# IVEEDRIS-SCIR.net
KiCad netlist of a schematic drawn in EAGLE
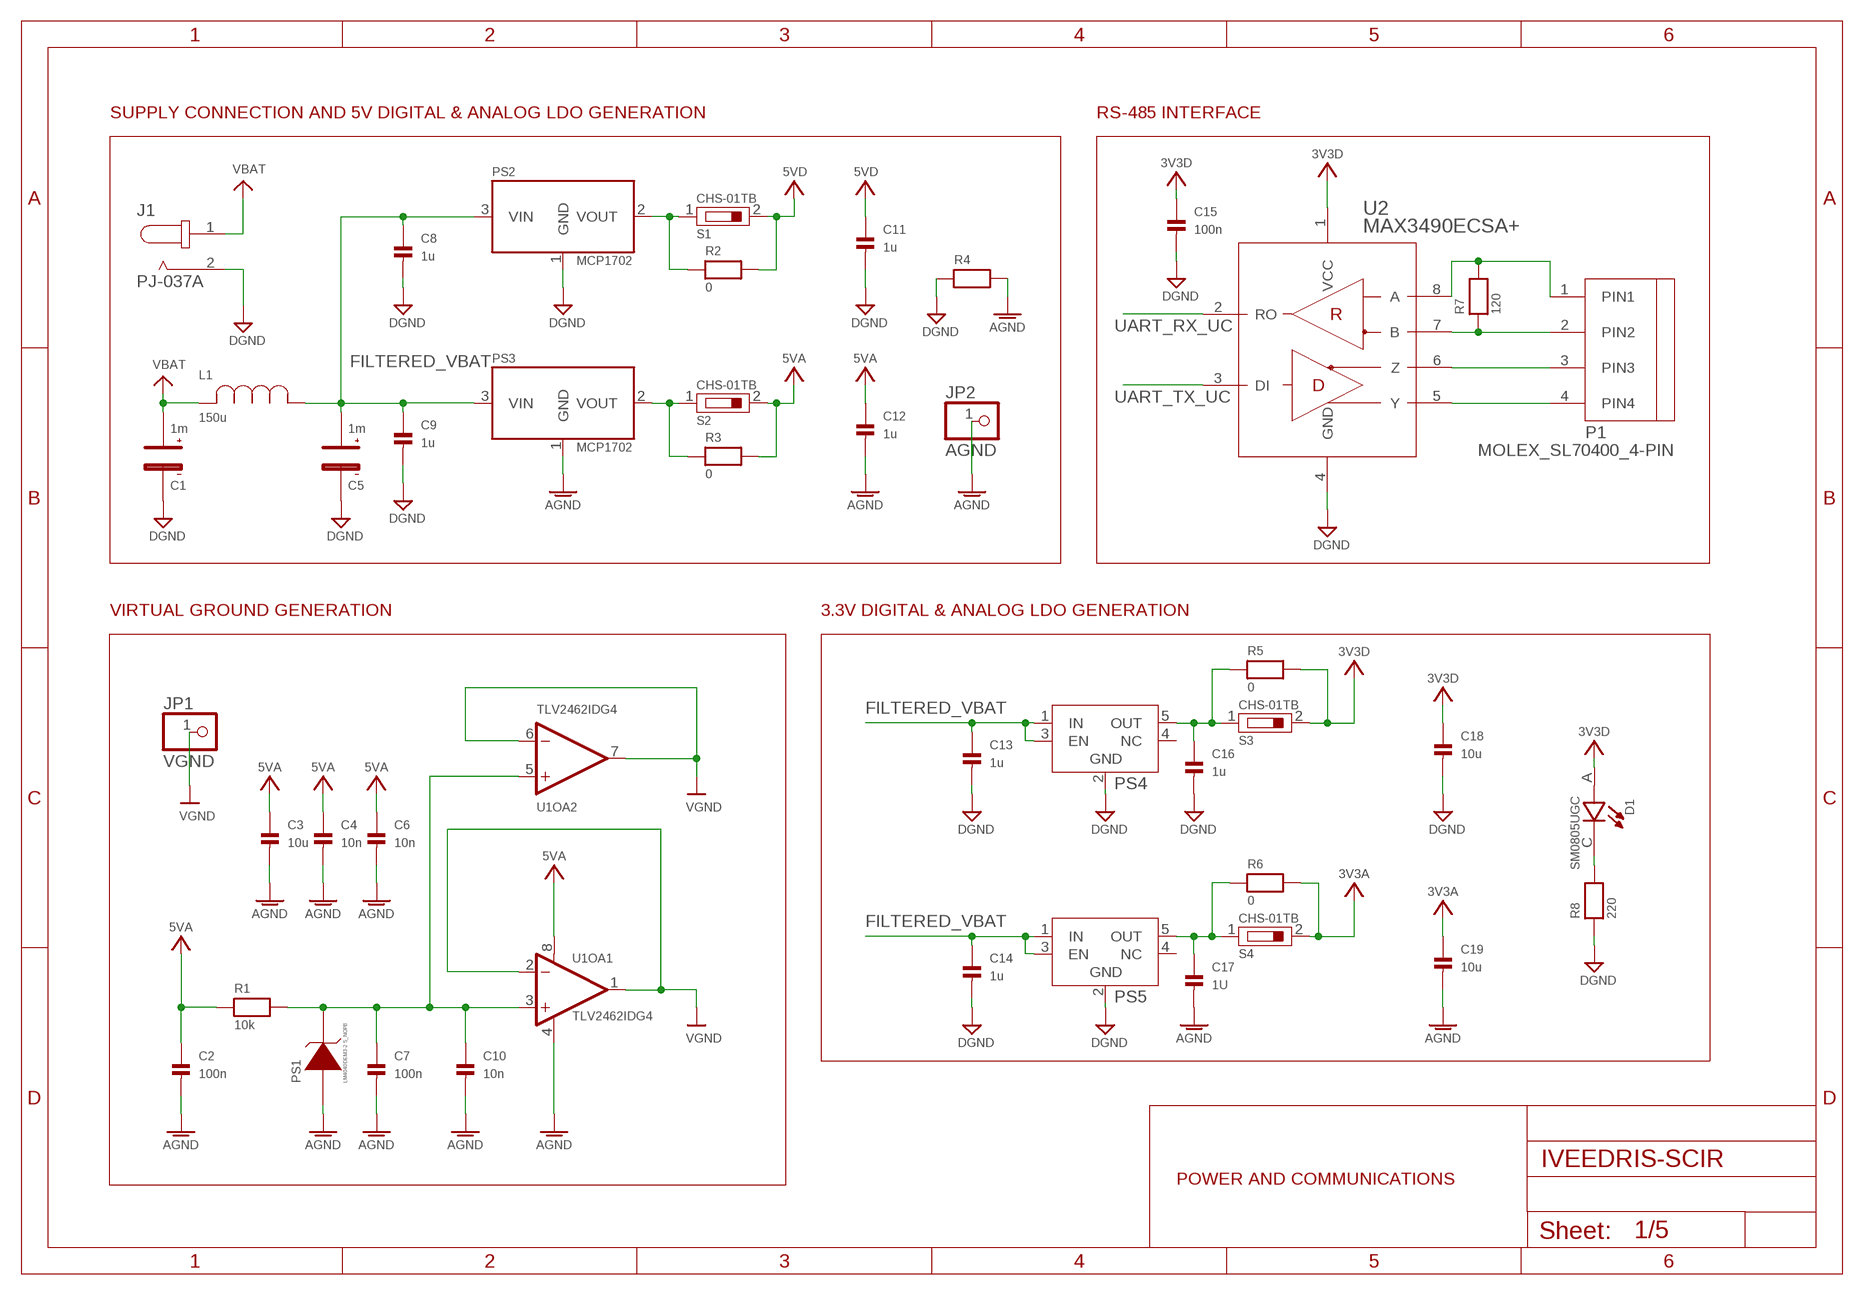
[diagram p0: schematic, sheet 1]
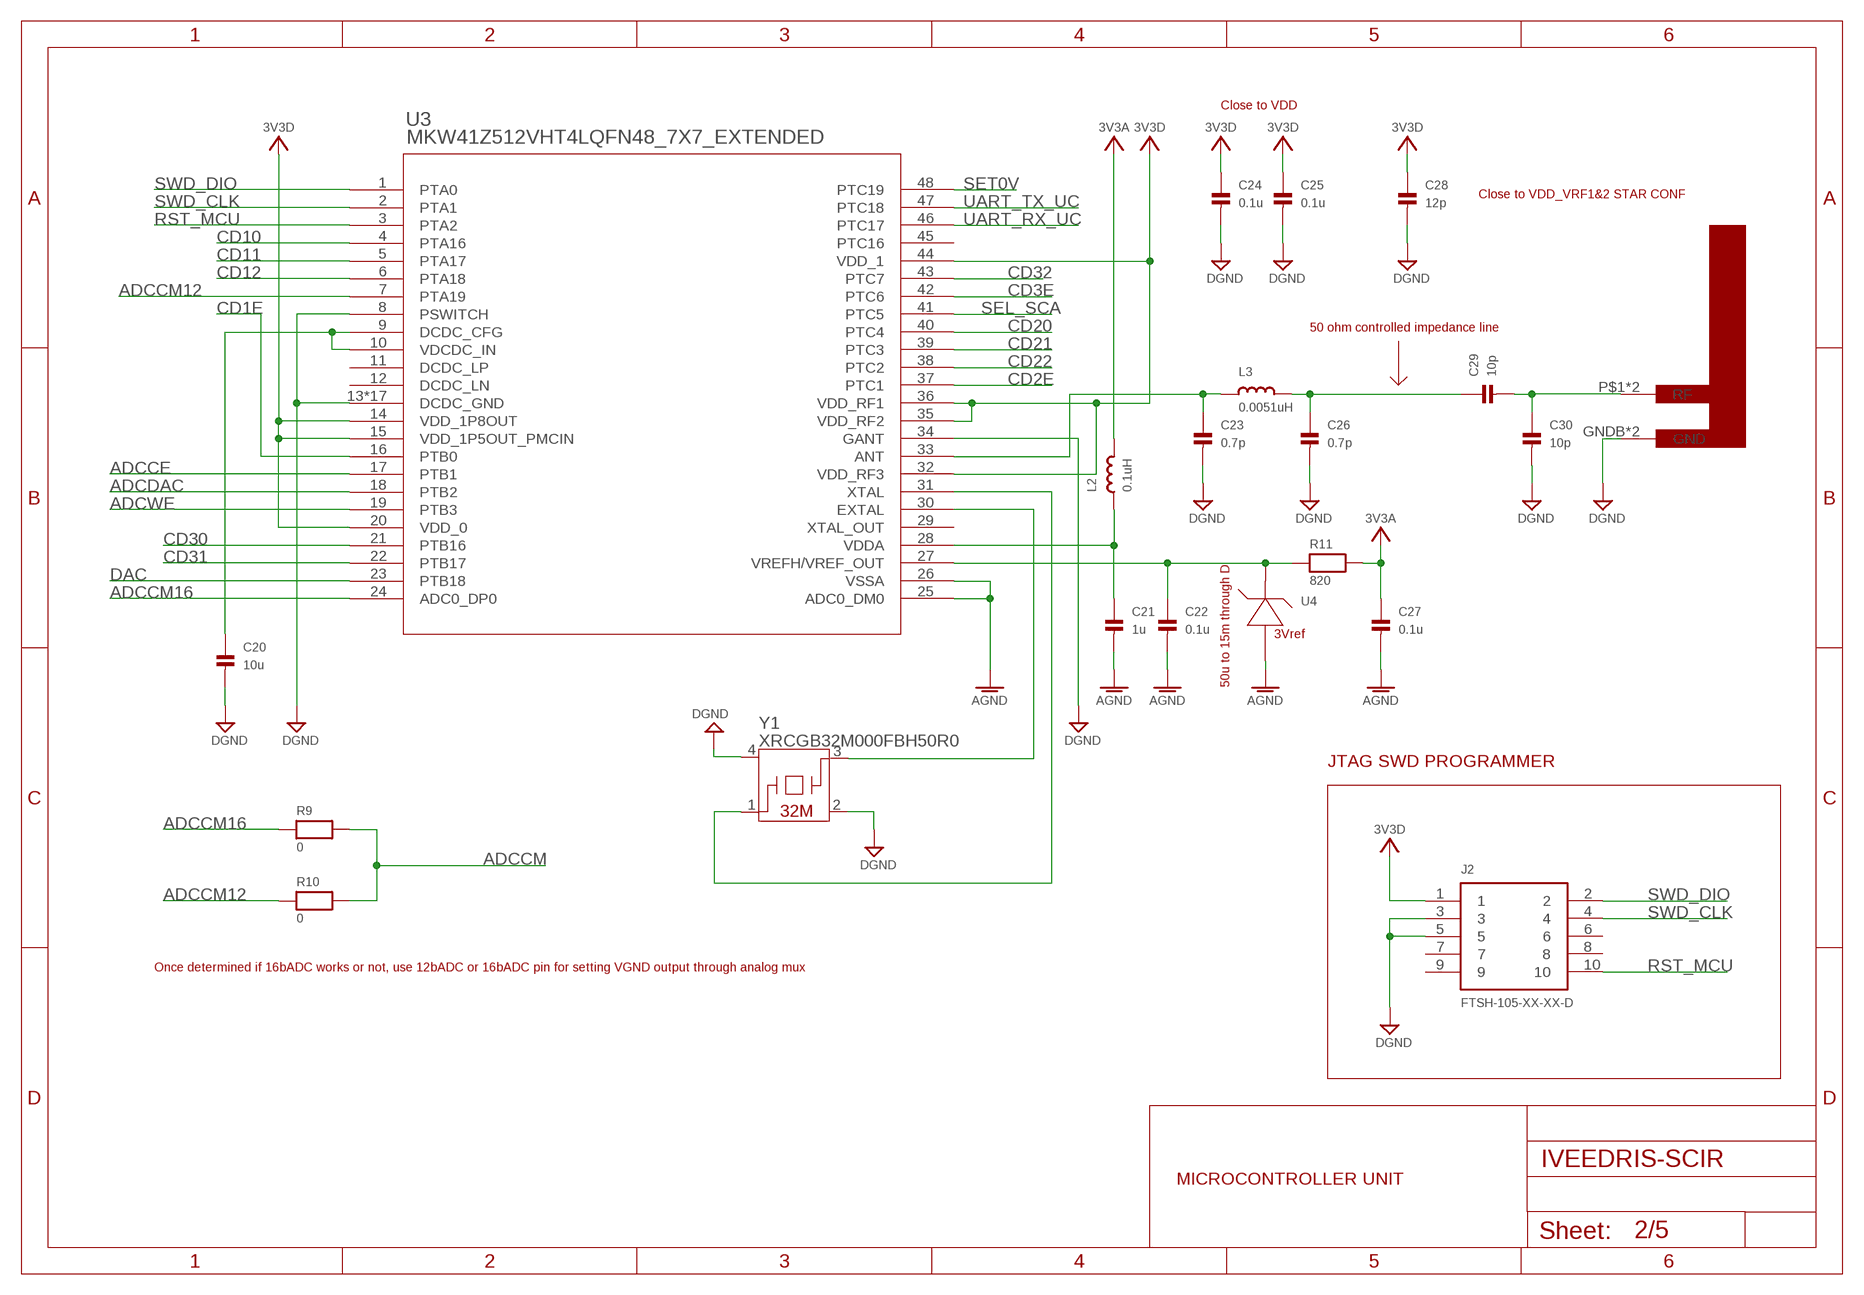
[diagram p1: schematic, sheet 2]
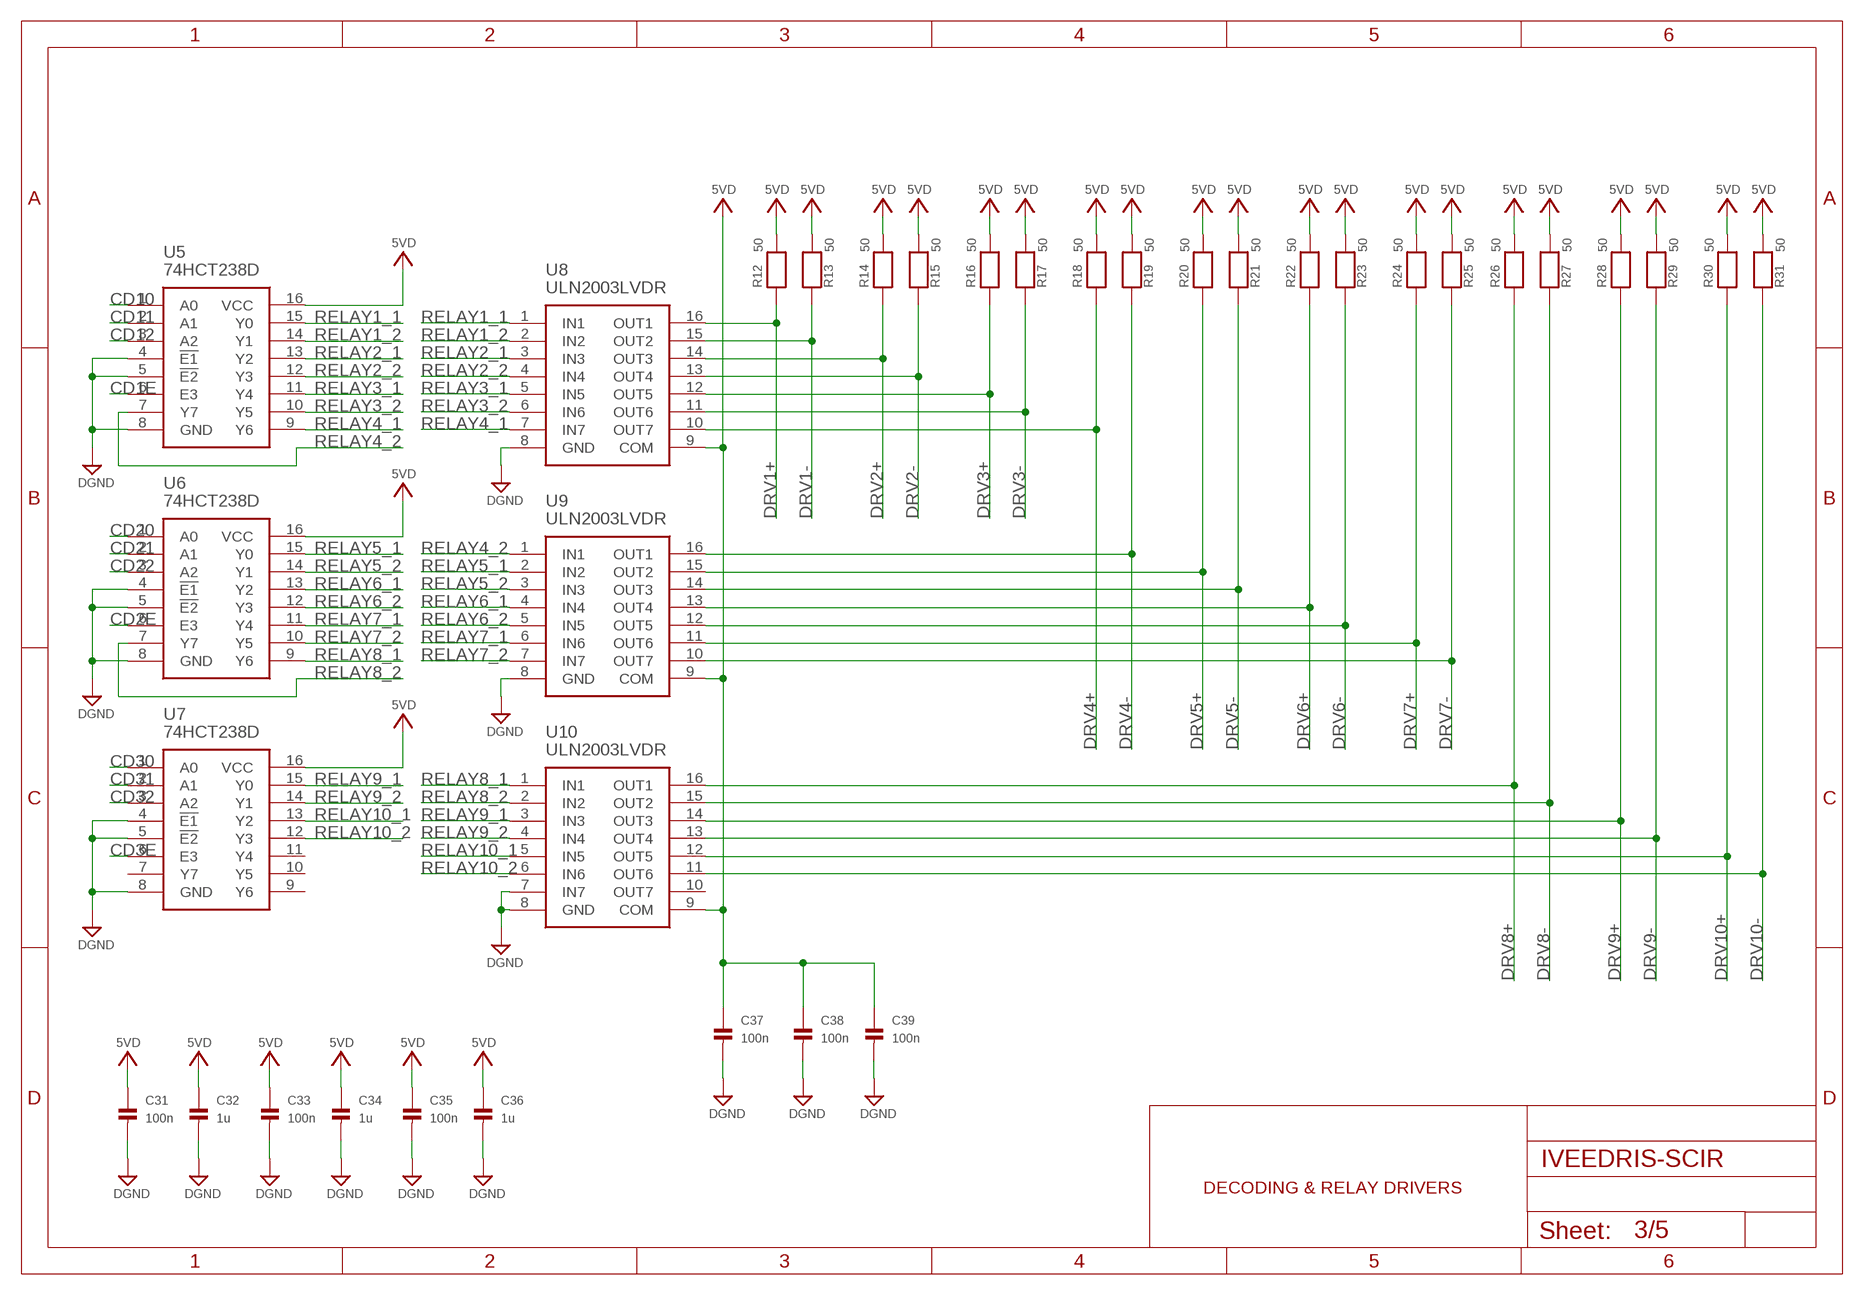
[diagram p2: schematic, sheet 3]
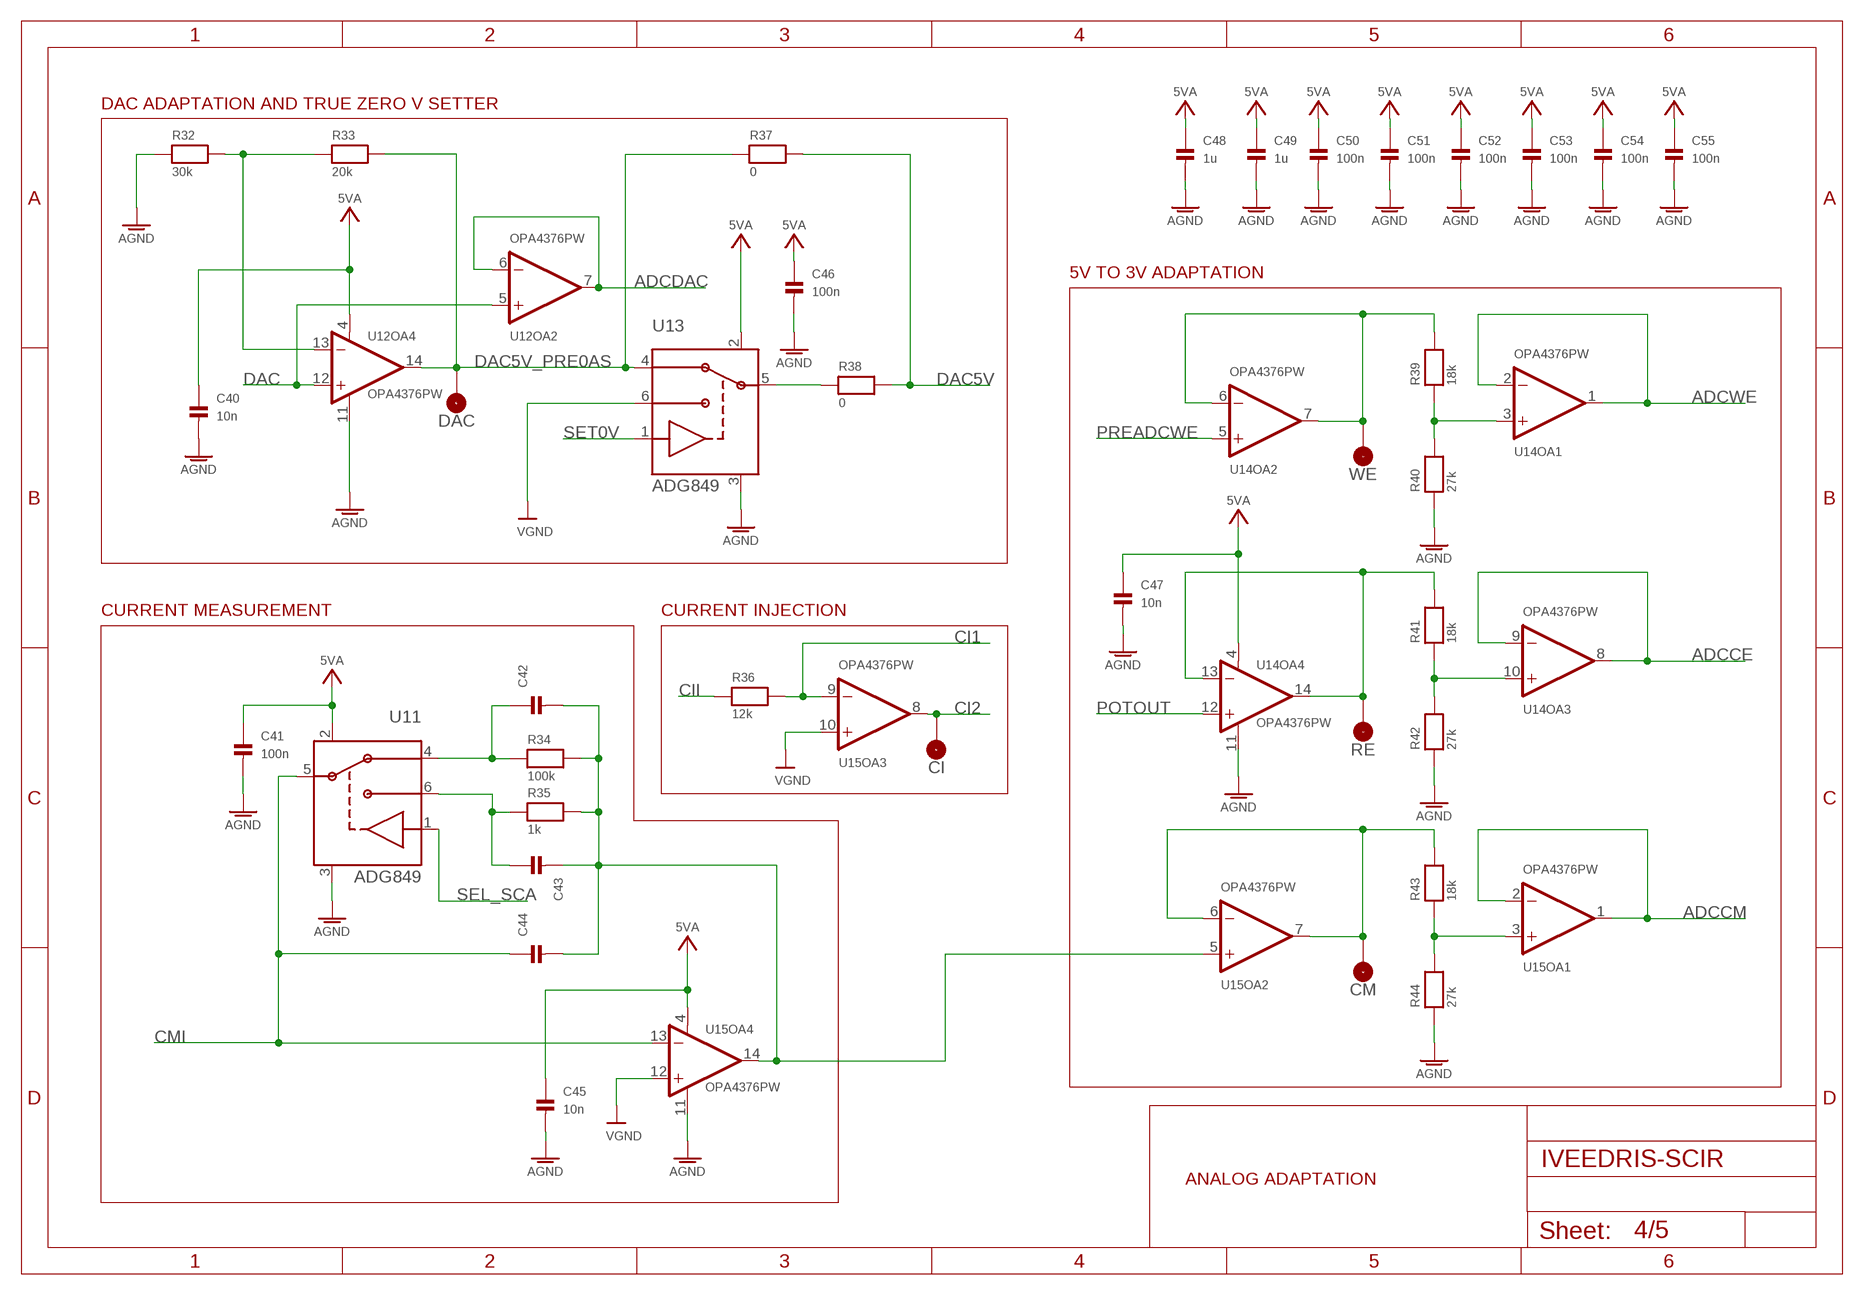
[diagram p3: schematic, sheet 4]
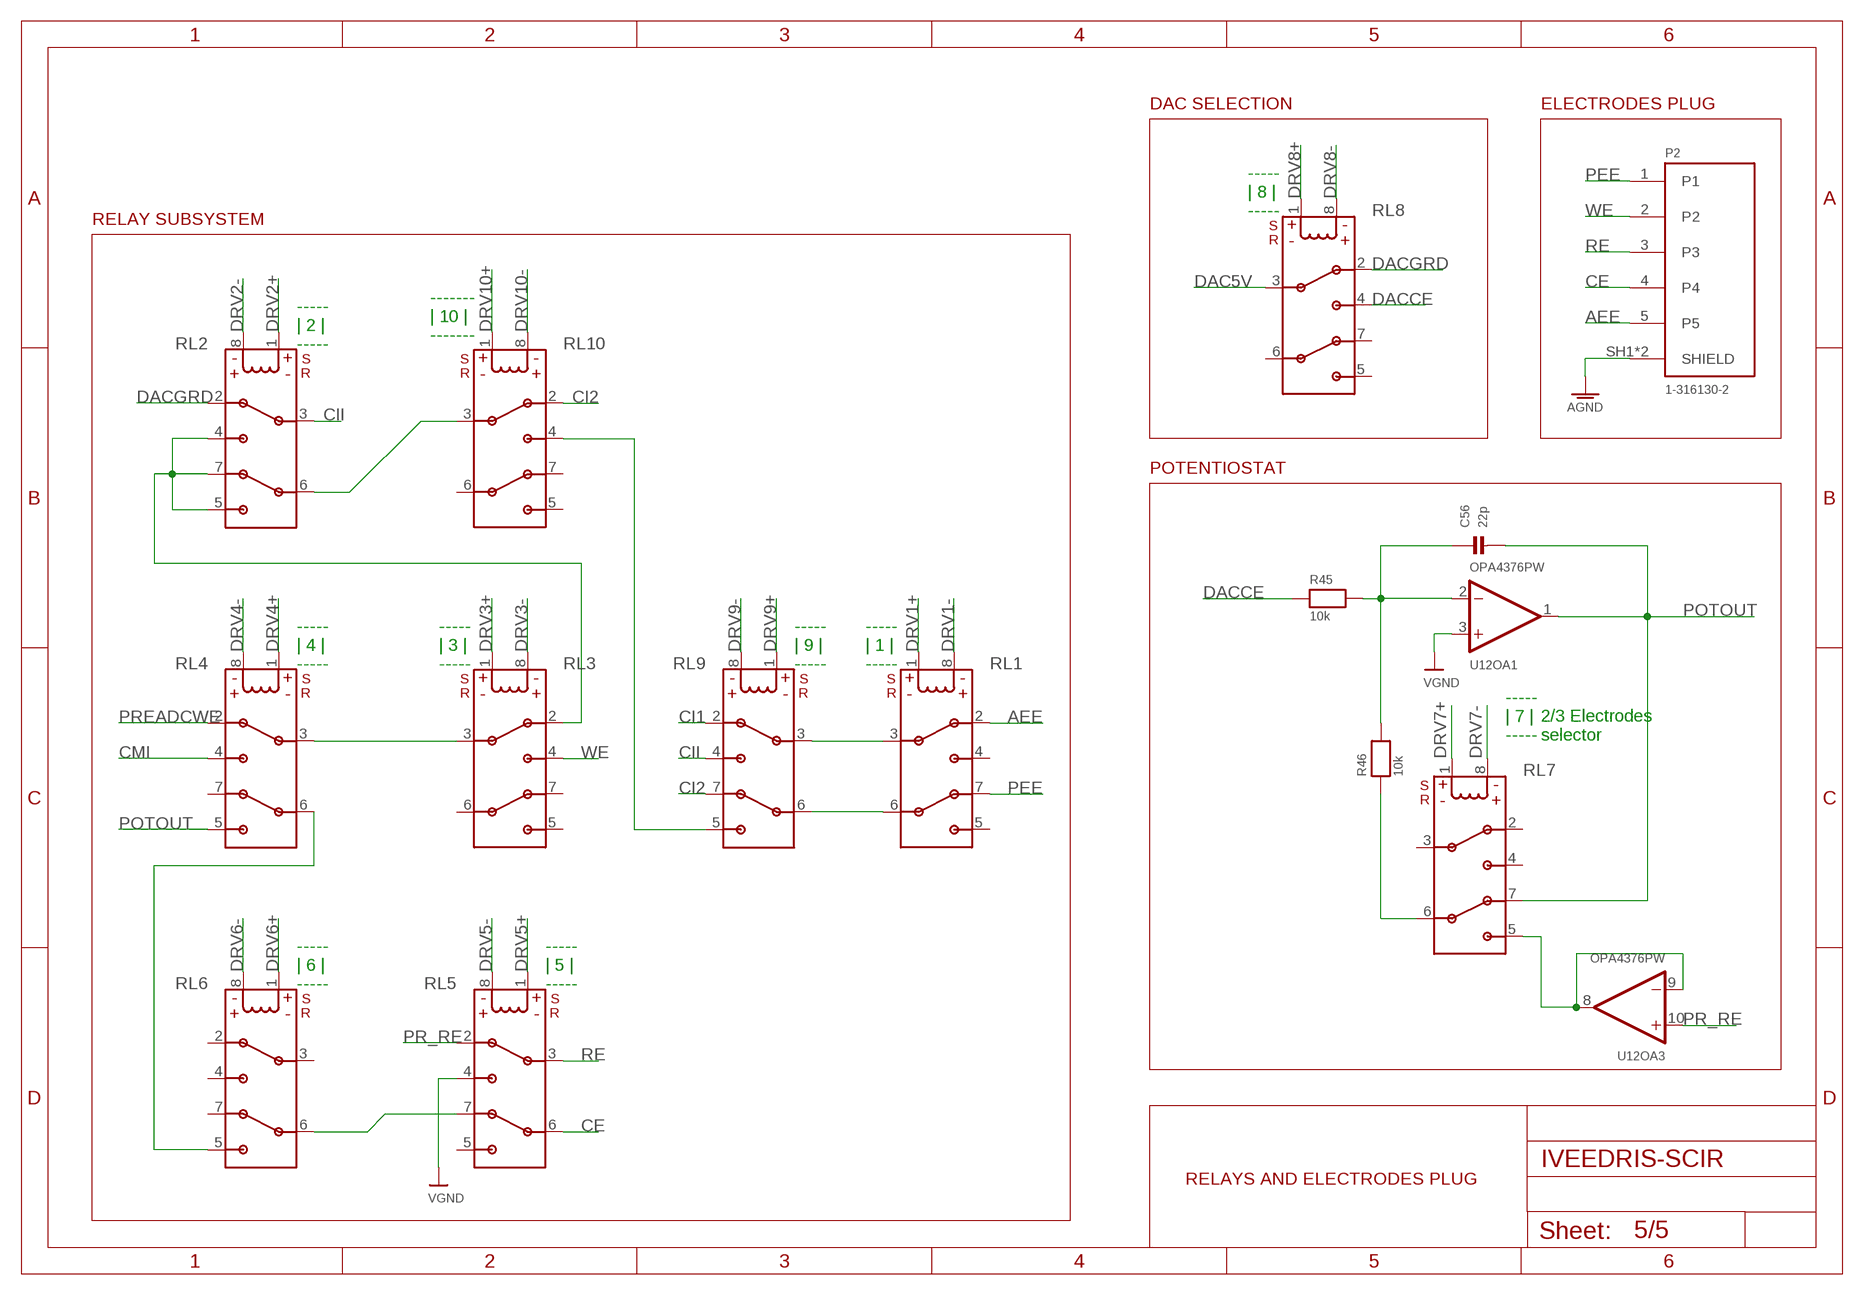
[diagram p4: schematic, sheet 5]

(export (version "E")
  (design (tool "Eeschema 10.0.6"))
  (components
    (comp (ref "C56")
      (value "22p")
      (footprint "eagle-import:0805")
      (libsource (lib "eagle-import") (part "CAP_CERAMIC0805"))
    )
    (comp (ref "P2")
      (value "1-316130-2")
      (footprint "eagle-import:TE_1-316130-2")
      (libsource (lib "eagle-import") (part "1-316130-2"))
    )
    (comp (ref "R45")
      (value "10k")
      (footprint "eagle-import:0805")
      (libsource (lib "eagle-import") (part "RESISTOR0805"))
    )
    (comp (ref "R46")
      (value "10k")
      (footprint "eagle-import:0805")
      (libsource (lib "eagle-import") (part "RESISTOR0805"))
    )
    (comp (ref "RL1")
      (value "G6KU-2F-Y")
      (footprint "eagle-import:G6KU-2F-Y")
      (fields (field (name "MANUFACTURER_PART_NUMBER") "G6KU-2F-Y DC5"))
      (libsource (lib "eagle-import") (part "G6KU-2F-Y"))
    )
    (comp (ref "RL2")
      (value "G6KU-2F-Y")
      (footprint "eagle-import:G6KU-2F-Y")
      (fields (field (name "MANUFACTURER_PART_NUMBER") "G6KU-2F-Y DC5"))
      (libsource (lib "eagle-import") (part "G6KU-2F-Y"))
    )
    (comp (ref "RL3")
      (value "G6KU-2F-Y")
      (footprint "eagle-import:G6KU-2F-Y")
      (fields (field (name "MANUFACTURER_PART_NUMBER") "G6KU-2F-Y DC5"))
      (libsource (lib "eagle-import") (part "G6KU-2F-Y"))
    )
    (comp (ref "RL4")
      (value "G6KU-2F-Y")
      (footprint "eagle-import:G6KU-2F-Y")
      (fields (field (name "MANUFACTURER_PART_NUMBER") "G6KU-2F-Y DC5"))
      (libsource (lib "eagle-import") (part "G6KU-2F-Y"))
    )
    (comp (ref "RL5")
      (value "G6KU-2F-Y")
      (footprint "eagle-import:G6KU-2F-Y")
      (fields (field (name "MANUFACTURER_PART_NUMBER") "G6KU-2F-Y DC5"))
      (libsource (lib "eagle-import") (part "G6KU-2F-Y"))
    )
    (comp (ref "RL6")
      (value "G6KU-2F-Y")
      (footprint "eagle-import:G6KU-2F-Y")
      (fields (field (name "MANUFACTURER_PART_NUMBER") "G6KU-2F-Y DC5"))
      (libsource (lib "eagle-import") (part "G6KU-2F-Y"))
    )
    (comp (ref "RL7")
      (value "G6KU-2F-Y")
      (footprint "eagle-import:G6KU-2F-Y")
      (fields (field (name "MANUFACTURER_PART_NUMBER") "G6KU-2F-Y DC5"))
      (libsource (lib "eagle-import") (part "G6KU-2F-Y"))
    )
    (comp (ref "RL8")
      (value "G6KU-2F-Y")
      (footprint "eagle-import:G6KU-2F-Y")
      (fields (field (name "MANUFACTURER_PART_NUMBER") "G6KU-2F-Y DC5"))
      (libsource (lib "eagle-import") (part "G6KU-2F-Y"))
    )
    (comp (ref "RL9")
      (value "G6KU-2F-Y")
      (footprint "eagle-import:G6KU-2F-Y")
      (fields (field (name "MANUFACTURER_PART_NUMBER") "G6KU-2F-Y DC5"))
      (libsource (lib "eagle-import") (part "G6KU-2F-Y"))
    )
    (comp (ref "RL10")
      (value "G6KU-2F-Y")
      (footprint "eagle-import:G6KU-2F-Y")
      (fields (field (name "MANUFACTURER_PART_NUMBER") "G6KU-2F-Y DC5"))
      (libsource (lib "eagle-import") (part "G6KU-2F-Y"))
    )
    (comp (ref "U12")
      (value "OPA4376PW")
      (footprint "eagle-import:TSSOP14-NOTHERMALPAD")
      (libsource (lib "eagle-import") (part "OPA4376PW"))
    )
    (comp (ref "C1")
      (value "1m")
      (footprint "eagle-import:CAP_ALUMINIUM")
      (libsource (lib "eagle-import") (part "APSG160ELL102MH20S"))
    )
    (comp (ref "C2")
      (value "100n")
      (footprint "eagle-import:0805")
      (libsource (lib "eagle-import") (part "CAP_CERAMIC0805"))
    )
    (comp (ref "C3")
      (value "10u")
      (footprint "eagle-import:0805")
      (libsource (lib "eagle-import") (part "CAP_CERAMIC0805"))
    )
    (comp (ref "C4")
      (value "10n")
      (footprint "eagle-import:0805")
      (libsource (lib "eagle-import") (part "CAP_CERAMIC0805"))
    )
    (comp (ref "C5")
      (value "1m")
      (footprint "eagle-import:CAP_ALUMINIUM")
      (libsource (lib "eagle-import") (part "APSG160ELL102MH20S"))
    )
    (comp (ref "C6")
      (value "10n")
      (footprint "eagle-import:0805")
      (libsource (lib "eagle-import") (part "CAP_CERAMIC0805"))
    )
    (comp (ref "C7")
      (value "100n")
      (footprint "eagle-import:0805")
      (libsource (lib "eagle-import") (part "CAP_CERAMIC0805"))
    )
    (comp (ref "C8")
      (value "1u")
      (footprint "eagle-import:0805")
      (libsource (lib "eagle-import") (part "CAP_CERAMIC0805"))
    )
    (comp (ref "C9")
      (value "1u")
      (footprint "eagle-import:0805")
      (libsource (lib "eagle-import") (part "CAP_CERAMIC0805"))
    )
    (comp (ref "C10")
      (value "10n")
      (footprint "eagle-import:0805")
      (libsource (lib "eagle-import") (part "CAP_CERAMIC0805"))
    )
    (comp (ref "C11")
      (value "1u")
      (footprint "eagle-import:0805")
      (libsource (lib "eagle-import") (part "CAP_CERAMIC0805"))
    )
    (comp (ref "C12")
      (value "1u")
      (footprint "eagle-import:0805")
      (libsource (lib "eagle-import") (part "CAP_CERAMIC0805"))
    )
    (comp (ref "C13")
      (value "1u")
      (footprint "eagle-import:0805")
      (libsource (lib "eagle-import") (part "CAP_CERAMIC0805"))
    )
    (comp (ref "C14")
      (value "1u")
      (footprint "eagle-import:0805")
      (libsource (lib "eagle-import") (part "CAP_CERAMIC0805"))
    )
    (comp (ref "C15")
      (value "100n")
      (footprint "eagle-import:0805")
      (libsource (lib "eagle-import") (part "CAP_CERAMIC0805"))
    )
    (comp (ref "C16")
      (value "1u")
      (footprint "eagle-import:0805")
      (libsource (lib "eagle-import") (part "CAP_CERAMIC0805"))
    )
    (comp (ref "C17")
      (value "1U")
      (footprint "eagle-import:0805")
      (libsource (lib "eagle-import") (part "CAP_CERAMIC0805"))
    )
    (comp (ref "C18")
      (value "10u")
      (footprint "eagle-import:0805")
      (libsource (lib "eagle-import") (part "CAP_CERAMIC0805"))
    )
    (comp (ref "C19")
      (value "10u")
      (footprint "eagle-import:0805")
      (libsource (lib "eagle-import") (part "CAP_CERAMIC0805"))
    )
    (comp (ref "D1")
      (value "SM0805UGC")
      (footprint "eagle-import:LEDC2012X135N")
      (libsource (lib "eagle-import") (part "SM0805UGC"))
    )
    (comp (ref "J1")
      (value "PJ-037A")
      (footprint "eagle-import:CUI_PJ-037A")
      (libsource (lib "eagle-import") (part "PJ-037A"))
    )
    (comp (ref "JP1")
      (value "VGND")
      (footprint "eagle-import:1X01_OVAL")
      (libsource (lib "eagle-import") (part "HEADER-1X1"))
    )
    (comp (ref "JP2")
      (value "AGND")
      (footprint "eagle-import:1X01_OVAL")
      (libsource (lib "eagle-import") (part "HEADER-1X1"))
    )
    (comp (ref "L1")
      (value "150u")
      (footprint "eagle-import:IND_PM3308-RC")
      (fields (field (name "MANUFACTURER_PART_NUMBER") "PM3308-151M-RC"))
      (libsource (lib "eagle-import") (part "PM3308-151M-RC"))
    )
    (comp (ref "P1")
      (value "MOLEX_SL70400_4-PIN")
      (footprint "eagle-import:MOLEX_SL70400_4-PIN")
      (fields (field (name "MANUFACTURER_PART_NUMBER") "0705530038"))
      (libsource (lib "eagle-import") (part "MOLEX_SL70400_4-PIN"))
    )
    (comp (ref "PS1")
      (value "LM4040DEM3-2.5_NOPB")
      (footprint "eagle-import:SOT95P237X112-3N")
      (fields (field (name "MANUFACTURER_PART_NUMBER") "LM4040DEM3X-2.5/NOPB"))
      (libsource (lib "eagle-import") (part "LM4040DEM3-2.5_NOPB"))
    )
    (comp (ref "PS2")
      (value "MCP1702")
      (footprint "eagle-import:SOT23-A")
      (libsource (lib "eagle-import") (part "MCP1702"))
    )
    (comp (ref "PS3")
      (value "MCP1702")
      (footprint "eagle-import:SOT23-A")
      (libsource (lib "eagle-import") (part "MCP1702"))
    )
    (comp (ref "PS4")
      (value "MCP1802T-3302I/OT")
      (footprint "eagle-import:TSOT-23_S5")
      (libsource (lib "eagle-import") (part "MCP1802T-3302I/OT"))
    )
    (comp (ref "PS5")
      (value "MCP1802T-3302I/OT")
      (footprint "eagle-import:TSOT-23_S5")
      (libsource (lib "eagle-import") (part "MCP1802T-3302I/OT"))
    )
    (comp (ref "R1")
      (value "10k")
      (footprint "eagle-import:0805")
      (libsource (lib "eagle-import") (part "RESISTOR0805"))
    )
    (comp (ref "R2")
      (value "0")
      (footprint "eagle-import:0805")
      (libsource (lib "eagle-import") (part "RESISTOR0805"))
    )
    (comp (ref "R3")
      (value "0")
      (footprint "eagle-import:0805")
      (libsource (lib "eagle-import") (part "RESISTOR0805"))
    )
    (comp (ref "R4")
      (value "RESISTOR0402")
      (footprint "eagle-import:0402")
      (libsource (lib "eagle-import") (part "RESISTOR0402"))
    )
    (comp (ref "R5")
      (value "0")
      (footprint "eagle-import:0805")
      (libsource (lib "eagle-import") (part "RESISTOR0805"))
    )
    (comp (ref "R6")
      (value "0")
      (footprint "eagle-import:0805")
      (libsource (lib "eagle-import") (part "RESISTOR0805"))
    )
    (comp (ref "R7")
      (value "120")
      (footprint "eagle-import:0805")
      (libsource (lib "eagle-import") (part "RESISTOR0805"))
    )
    (comp (ref "R8")
      (value "220")
      (footprint "eagle-import:0805")
      (libsource (lib "eagle-import") (part "RESISTOR0805"))
    )
    (comp (ref "S1")
      (value "CHS-01TB")
      (footprint "eagle-import:CHS-01TB")
      (libsource (lib "eagle-import") (part "CHS-01TB"))
    )
    (comp (ref "S2")
      (value "CHS-01TB")
      (footprint "eagle-import:CHS-01TB")
      (libsource (lib "eagle-import") (part "CHS-01TB"))
    )
    (comp (ref "S3")
      (value "CHS-01TB")
      (footprint "eagle-import:CHS-01TB")
      (libsource (lib "eagle-import") (part "CHS-01TB"))
    )
    (comp (ref "S4")
      (value "CHS-01TB")
      (footprint "eagle-import:CHS-01TB")
      (libsource (lib "eagle-import") (part "CHS-01TB"))
    )
    (comp (ref "U1")
      (value "TLV2462IDG4")
      (footprint "eagle-import:SO8")
      (fields (field (name "MANUFACTURER_PART_NUMBER") "TLV2462AQDRQ1"))
      (libsource (lib "eagle-import") (part "TLV2462IDG4"))
    )
    (comp (ref "U2")
      (value "MAX3490ECSA+")
      (footprint "eagle-import:SOIC127P600X175-8N")
      (libsource (lib "eagle-import") (part "MAX3490ECSA+"))
    )
    (comp (ref "C31")
      (value "100n")
      (footprint "eagle-import:0805")
      (libsource (lib "eagle-import") (part "CAP_CERAMIC0805"))
    )
    (comp (ref "C32")
      (value "1u")
      (footprint "eagle-import:0805")
      (libsource (lib "eagle-import") (part "CAP_CERAMIC0805"))
    )
    (comp (ref "C33")
      (value "100n")
      (footprint "eagle-import:0805")
      (libsource (lib "eagle-import") (part "CAP_CERAMIC0805"))
    )
    (comp (ref "C34")
      (value "1u")
      (footprint "eagle-import:0805")
      (libsource (lib "eagle-import") (part "CAP_CERAMIC0805"))
    )
    (comp (ref "C35")
      (value "100n")
      (footprint "eagle-import:0805")
      (libsource (lib "eagle-import") (part "CAP_CERAMIC0805"))
    )
    (comp (ref "C36")
      (value "1u")
      (footprint "eagle-import:0805")
      (libsource (lib "eagle-import") (part "CAP_CERAMIC0805"))
    )
    (comp (ref "C37")
      (value "100n")
      (footprint "eagle-import:0805")
      (libsource (lib "eagle-import") (part "CAP_CERAMIC0805"))
    )
    (comp (ref "C38")
      (value "100n")
      (footprint "eagle-import:0805")
      (libsource (lib "eagle-import") (part "CAP_CERAMIC0805"))
    )
    (comp (ref "C39")
      (value "100n")
      (footprint "eagle-import:0805")
      (libsource (lib "eagle-import") (part "CAP_CERAMIC0805"))
    )
    (comp (ref "R12")
      (value "50")
      (footprint "eagle-import:0805")
      (libsource (lib "eagle-import") (part "RESISTOR0805"))
    )
    (comp (ref "R13")
      (value "50")
      (footprint "eagle-import:0805")
      (libsource (lib "eagle-import") (part "RESISTOR0805"))
    )
    (comp (ref "R14")
      (value "50")
      (footprint "eagle-import:0805")
      (libsource (lib "eagle-import") (part "RESISTOR0805"))
    )
    (comp (ref "R15")
      (value "50")
      (footprint "eagle-import:0805")
      (libsource (lib "eagle-import") (part "RESISTOR0805"))
    )
    (comp (ref "R16")
      (value "50")
      (footprint "eagle-import:0805")
      (libsource (lib "eagle-import") (part "RESISTOR0805"))
    )
    (comp (ref "R17")
      (value "50")
      (footprint "eagle-import:0805")
      (libsource (lib "eagle-import") (part "RESISTOR0805"))
    )
    (comp (ref "R18")
      (value "50")
      (footprint "eagle-import:0805")
      (libsource (lib "eagle-import") (part "RESISTOR0805"))
    )
    (comp (ref "R19")
      (value "50")
      (footprint "eagle-import:0805")
      (libsource (lib "eagle-import") (part "RESISTOR0805"))
    )
    (comp (ref "R20")
      (value "50")
      (footprint "eagle-import:0805")
      (libsource (lib "eagle-import") (part "RESISTOR0805"))
    )
    (comp (ref "R21")
      (value "50")
      (footprint "eagle-import:0805")
      (libsource (lib "eagle-import") (part "RESISTOR0805"))
    )
    (comp (ref "R22")
      (value "50")
      (footprint "eagle-import:0805")
      (libsource (lib "eagle-import") (part "RESISTOR0805"))
    )
    (comp (ref "R23")
      (value "50")
      (footprint "eagle-import:0805")
      (libsource (lib "eagle-import") (part "RESISTOR0805"))
    )
    (comp (ref "R24")
      (value "50")
      (footprint "eagle-import:0805")
      (libsource (lib "eagle-import") (part "RESISTOR0805"))
    )
    (comp (ref "R25")
      (value "50")
      (footprint "eagle-import:0805")
      (libsource (lib "eagle-import") (part "RESISTOR0805"))
    )
    (comp (ref "R26")
      (value "50")
      (footprint "eagle-import:0805")
      (libsource (lib "eagle-import") (part "RESISTOR0805"))
    )
    (comp (ref "R27")
      (value "50")
      (footprint "eagle-import:0805")
      (libsource (lib "eagle-import") (part "RESISTOR0805"))
    )
    (comp (ref "R28")
      (value "50")
      (footprint "eagle-import:0805")
      (libsource (lib "eagle-import") (part "RESISTOR0805"))
    )
    (comp (ref "R29")
      (value "50")
      (footprint "eagle-import:0805")
      (libsource (lib "eagle-import") (part "RESISTOR0805"))
    )
    (comp (ref "R30")
      (value "50")
      (footprint "eagle-import:0805")
      (libsource (lib "eagle-import") (part "RESISTOR0805"))
    )
    (comp (ref "R31")
      (value "50")
      (footprint "eagle-import:0805")
      (libsource (lib "eagle-import") (part "RESISTOR0805"))
    )
    (comp (ref "U5")
      (value "74HCT238D")
      (footprint "eagle-import:SOIC127P600X175-16N")
      (fields (field (name "MANUFACTURER_PART_NUMBER") "74HCT238D,652"))
      (libsource (lib "eagle-import") (part "74HCT238D"))
    )
    (comp (ref "U6")
      (value "74HCT238D")
      (footprint "eagle-import:SOIC127P600X175-16N")
      (fields (field (name "MANUFACTURER_PART_NUMBER") "74HCT238D,652"))
      (libsource (lib "eagle-import") (part "74HCT238D"))
    )
    (comp (ref "U7")
      (value "74HCT238D")
      (footprint "eagle-import:SOIC127P600X175-16N")
      (fields (field (name "MANUFACTURER_PART_NUMBER") "74HCT238D,652"))
      (libsource (lib "eagle-import") (part "74HCT238D"))
    )
    (comp (ref "U8")
      (value "ULN2003LVDR")
      (footprint "eagle-import:SOIC127P600X175-16N")
      (libsource (lib "eagle-import") (part "ULN2003LVDR"))
    )
    (comp (ref "U9")
      (value "ULN2003LVDR")
      (footprint "eagle-import:SOIC127P600X175-16N")
      (libsource (lib "eagle-import") (part "ULN2003LVDR"))
    )
    (comp (ref "U10")
      (value "ULN2003LVDR")
      (footprint "eagle-import:SOIC127P600X175-16N")
      (libsource (lib "eagle-import") (part "ULN2003LVDR"))
    )
    (comp (ref "C40")
      (value "10n")
      (footprint "eagle-import:0805")
      (libsource (lib "eagle-import") (part "CAP_CERAMIC0805"))
    )
    (comp (ref "C41")
      (value "100n")
      (footprint "eagle-import:0805")
      (libsource (lib "eagle-import") (part "CAP_CERAMIC0805"))
    )
    (comp (ref "C42")
      (value "CAP_CERAMIC0805")
      (footprint "eagle-import:0805")
      (libsource (lib "eagle-import") (part "CAP_CERAMIC0805"))
    )
    (comp (ref "C43")
      (value "CAP_CERAMIC0805")
      (footprint "eagle-import:0805")
      (libsource (lib "eagle-import") (part "CAP_CERAMIC0805"))
    )
    (comp (ref "C44")
      (value "CAP_CERAMIC0805")
      (footprint "eagle-import:0805")
      (libsource (lib "eagle-import") (part "CAP_CERAMIC0805"))
    )
    (comp (ref "C45")
      (value "10n")
      (footprint "eagle-import:0805")
      (libsource (lib "eagle-import") (part "CAP_CERAMIC0805"))
    )
    (comp (ref "C46")
      (value "100n")
      (footprint "eagle-import:0805")
      (libsource (lib "eagle-import") (part "CAP_CERAMIC0805"))
    )
    (comp (ref "C47")
      (value "10n")
      (footprint "eagle-import:0805")
      (libsource (lib "eagle-import") (part "CAP_CERAMIC0805"))
    )
    (comp (ref "C48")
      (value "1u")
      (footprint "eagle-import:0805")
      (libsource (lib "eagle-import") (part "CAP_CERAMIC0805"))
    )
    (comp (ref "C49")
      (value "1u")
      (footprint "eagle-import:0805")
      (libsource (lib "eagle-import") (part "CAP_CERAMIC0805"))
    )
    (comp (ref "C50")
      (value "100n")
      (footprint "eagle-import:0805")
      (libsource (lib "eagle-import") (part "CAP_CERAMIC0805"))
    )
    (comp (ref "C51")
      (value "100n")
      (footprint "eagle-import:0805")
      (libsource (lib "eagle-import") (part "CAP_CERAMIC0805"))
    )
    (comp (ref "C52")
      (value "100n")
      (footprint "eagle-import:0805")
      (libsource (lib "eagle-import") (part "CAP_CERAMIC0805"))
    )
    (comp (ref "C53")
      (value "100n")
      (footprint "eagle-import:0805")
      (libsource (lib "eagle-import") (part "CAP_CERAMIC0805"))
    )
    (comp (ref "C54")
      (value "100n")
      (footprint "eagle-import:0805")
      (libsource (lib "eagle-import") (part "CAP_CERAMIC0805"))
    )
    (comp (ref "C55")
      (value "100n")
      (footprint "eagle-import:0805")
      (libsource (lib "eagle-import") (part "CAP_CERAMIC0805"))
    )
    (comp (ref "CI")
      (value "TESTPOINT")
      (footprint "eagle-import:NOSOLDERPAD")
      (libsource (lib "eagle-import") (part "TESTPOINT"))
    )
    (comp (ref "CM")
      (value "TESTPOINT")
      (footprint "eagle-import:NOSOLDERPAD")
      (libsource (lib "eagle-import") (part "TESTPOINT"))
    )
    (comp (ref "DAC")
      (value "TESTPOINT")
      (footprint "eagle-import:NOSOLDERPAD")
      (libsource (lib "eagle-import") (part "TESTPOINT"))
    )
    (comp (ref "R32")
      (value "30k")
      (footprint "eagle-import:0805")
      (libsource (lib "eagle-import") (part "RESISTOR0805"))
    )
    (comp (ref "R33")
      (value "20k")
      (footprint "eagle-import:0805")
      (libsource (lib "eagle-import") (part "RESISTOR0805"))
    )
    (comp (ref "R34")
      (value "100k")
      (footprint "eagle-import:1206")
      (libsource (lib "eagle-import") (part "RESISTOR1206"))
    )
    (comp (ref "R35")
      (value "1k")
      (footprint "eagle-import:1206")
      (libsource (lib "eagle-import") (part "RESISTOR1206"))
    )
    (comp (ref "R36")
      (value "12k")
      (footprint "eagle-import:1206")
      (libsource (lib "eagle-import") (part "RESISTOR1206"))
    )
    (comp (ref "R37")
      (value "0")
      (footprint "eagle-import:0805")
      (libsource (lib "eagle-import") (part "RESISTOR0805"))
    )
    (comp (ref "R38")
      (value "0")
      (footprint "eagle-import:0805")
      (libsource (lib "eagle-import") (part "RESISTOR0805"))
    )
    (comp (ref "R39")
      (value "18k")
      (footprint "eagle-import:0805")
      (libsource (lib "eagle-import") (part "RESISTOR0805"))
    )
    (comp (ref "R40")
      (value "27k")
      (footprint "eagle-import:0805")
      (libsource (lib "eagle-import") (part "RESISTOR0805"))
    )
    (comp (ref "R41")
      (value "18k")
      (footprint "eagle-import:0805")
      (fields (field (name "SPICEPREFIX") "R"))
      (libsource (lib "eagle-import") (part "RESISTOR0805"))
    )
    (comp (ref "R42")
      (value "27k")
      (footprint "eagle-import:0805")
      (libsource (lib "eagle-import") (part "RESISTOR0805"))
    )
    (comp (ref "R43")
      (value "18k")
      (footprint "eagle-import:0805")
      (libsource (lib "eagle-import") (part "RESISTOR0805"))
    )
    (comp (ref "R44")
      (value "27k")
      (footprint "eagle-import:0805")
      (libsource (lib "eagle-import") (part "RESISTOR0805"))
    )
    (comp (ref "RE")
      (value "TESTPOINT")
      (footprint "eagle-import:NOSOLDERPAD")
      (libsource (lib "eagle-import") (part "TESTPOINT"))
    )
    (comp (ref "U11")
      (value "ADG849")
      (footprint "eagle-import:SC70-6L")
      (fields (field (name "MANUFACTURER_PART_NUMBER") "ADG849YKSZ-500RL7"))
      (libsource (lib "eagle-import") (part "ADG849"))
    )
    (comp (ref "U13")
      (value "ADG849")
      (footprint "eagle-import:SC70-6L")
      (fields (field (name "MANUFACTURER_PART_NUMBER") "ADG849YKSZ-500RL7"))
      (libsource (lib "eagle-import") (part "ADG849"))
    )
    (comp (ref "U14")
      (value "OPA4376PW")
      (footprint "eagle-import:TSSOP14-NOTHERMALPAD")
      (libsource (lib "eagle-import") (part "OPA4376PW"))
    )
    (comp (ref "U15")
      (value "OPA4376PW")
      (footprint "eagle-import:TSSOP14-NOTHERMALPAD")
      (libsource (lib "eagle-import") (part "OPA4376PW"))
    )
    (comp (ref "WE")
      (value "TESTPOINT")
      (footprint "eagle-import:NOSOLDERPAD")
      (libsource (lib "eagle-import") (part "TESTPOINT"))
    )
    (comp (ref "AE1")
      (value "F_INVERTED_ANTENNA_2.4G")
      (footprint "eagle-import:RF2.4GHZ_FINVERTED_ANTENNA")
      (libsource (lib "eagle-import") (part "F_INVERTED_ANTENNA_2.4G"))
    )
    (comp (ref "C20")
      (value "10u")
      (footprint "eagle-import:0805")
      (libsource (lib "eagle-import") (part "CAP_CERAMIC0805"))
    )
    (comp (ref "C21")
      (value "1u")
      (footprint "eagle-import:0805")
      (libsource (lib "eagle-import") (part "CAP_CERAMIC0805"))
    )
    (comp (ref "C22")
      (value "0.1u")
      (footprint "eagle-import:0805")
      (libsource (lib "eagle-import") (part "CAP_CERAMIC0805"))
    )
    (comp (ref "C23")
      (value "0.7p")
      (footprint "eagle-import:0805")
      (libsource (lib "eagle-import") (part "CAP_CERAMIC0805"))
    )
    (comp (ref "C24")
      (value "0.1u")
      (footprint "eagle-import:0805")
      (libsource (lib "eagle-import") (part "CAP_CERAMIC0805"))
    )
    (comp (ref "C25")
      (value "0.1u")
      (footprint "eagle-import:0805")
      (libsource (lib "eagle-import") (part "CAP_CERAMIC0805"))
    )
    (comp (ref "C26")
      (value "0.7p")
      (footprint "eagle-import:0805")
      (libsource (lib "eagle-import") (part "CAP_CERAMIC0805"))
    )
    (comp (ref "C27")
      (value "0.1u")
      (footprint "eagle-import:0805")
      (libsource (lib "eagle-import") (part "CAP_CERAMIC0805"))
    )
    (comp (ref "C28")
      (value "12p")
      (footprint "eagle-import:0805")
      (libsource (lib "eagle-import") (part "CAP_CERAMIC0805"))
    )
    (comp (ref "C29")
      (value "10p")
      (footprint "eagle-import:0805")
      (libsource (lib "eagle-import") (part "CAP_CERAMIC0805"))
    )
    (comp (ref "C30")
      (value "10p")
      (footprint "eagle-import:0805")
      (libsource (lib "eagle-import") (part "CAP_CERAMIC0805"))
    )
    (comp (ref "J2")
      (value "FTSH-105-XX-XX-D")
      (footprint "eagle-import:FTSH-105-XX-XX-D")
      (libsource (lib "eagle-import") (part "FTSH-105-XX-XX-D"))
    )
    (comp (ref "L2")
      (value "0.1uH")
      (footprint "eagle-import:0805")
      (libsource (lib "eagle-import") (part "INDUCTOR0805"))
    )
    (comp (ref "L3")
      (value "0.0051uH")
      (footprint "eagle-import:0805")
      (libsource (lib "eagle-import") (part "INDUCTOR0805"))
    )
    (comp (ref "R9")
      (value "0")
      (footprint "eagle-import:0805")
      (libsource (lib "eagle-import") (part "RESISTOR0805"))
    )
    (comp (ref "R10")
      (value "0")
      (footprint "eagle-import:0805")
      (libsource (lib "eagle-import") (part "RESISTOR0805"))
    )
    (comp (ref "R11")
      (value "820")
      (footprint "eagle-import:0805")
      (libsource (lib "eagle-import") (part "RESISTOR0805"))
    )
    (comp (ref "U3")
      (value "MKW41Z512VHT4LQFN48_7X7_EXTENDED")
      (footprint "eagle-import:LQFN48_7X7_EXTENDED")
      (libsource (lib "eagle-import") (part "MKW41Z512VHT4LQFN48_7X7_EXTENDED"))
    )
    (comp (ref "U4")
      (value "ADR5043BKSZ-REEL7KS_3_ADI-M")
      (footprint "eagle-import:KS_3_ADI-M")
      (fields
        (field (name "MANUFACTURER_PART_NUMBER") "ADR5043BKSZ-REEL7")
        (field (name "COPYRIGHT") "Copyright (C) 2016 Accelerated Designs. All rights reserved")
      )
      (libsource (lib "eagle-import") (part "ADR5043BKSZ-REEL7KS_3_ADI-M"))
    )
    (comp (ref "Y1")
      (value "XRCGB32M000FBH50R0")
      (footprint "eagle-import:XRCGB32_F")
      (libsource (lib "eagle-import") (part "XRCGB32M000FBH50R0"))
    )
  )
  (nets
    (net (code "1") (name "3V3A") (class "Default")
      (node (ref "C19") (pin "1") (pinfunction "P$1_1") (pintype "passive"))
      (node (ref "C27") (pin "1") (pinfunction "P$1_1") (pintype "passive"))
      (node (ref "L2") (pin "2") (pinfunction "2_2") (pintype "passive"))
      (node (ref "R11") (pin "2") (pinfunction "2_2") (pintype "passive"))
      (node (ref "R6") (pin "2") (pinfunction "2_2") (pintype "passive"))
      (node (ref "S4") (pin "2") (pinfunction "P$2_2") (pintype "bidirectional"))
    )
    (net (code "2") (name "3V3D") (class "Default")
      (node (ref "C15") (pin "1") (pinfunction "P$1_1") (pintype "passive"))
      (node (ref "C18") (pin "1") (pinfunction "P$1_1") (pintype "passive"))
      (node (ref "C24") (pin "1") (pinfunction "P$1_1") (pintype "passive"))
      (node (ref "C25") (pin "1") (pinfunction "P$1_1") (pintype "passive"))
      (node (ref "C28") (pin "1") (pinfunction "P$1_1") (pintype "passive"))
      (node (ref "D1") (pin "A") (pinfunction "A_A") (pintype "passive"))
      (node (ref "J2") (pin "1") (pinfunction "1_1") (pintype "bidirectional"))
      (node (ref "R5") (pin "2") (pinfunction "2_2") (pintype "passive"))
      (node (ref "S3") (pin "2") (pinfunction "P$2_2") (pintype "bidirectional"))
      (node (ref "U2") (pin "1") (pinfunction "VCC_1") (pintype "power_in"))
      (node (ref "U3") (pin "14") (pinfunction "VDD_1P8OUT_14") (pintype "power_in"))
      (node (ref "U3") (pin "15") (pinfunction "VDD_1P5OUT_PMCIN_15") (pintype "passive"))
      (node (ref "U3") (pin "20") (pinfunction "VDD_0_20") (pintype "power_in"))
      (node (ref "U3") (pin "32") (pinfunction "VDD_RF3_32") (pintype "power_in"))
      (node (ref "U3") (pin "35") (pinfunction "VDD_RF2_35") (pintype "power_in"))
      (node (ref "U3") (pin "36") (pinfunction "VDD_RF1_36") (pintype "power_in"))
      (node (ref "U3") (pin "44") (pinfunction "VDD_1_44") (pintype "power_in"))
    )
    (net (code "3") (name "5VA") (class "Default")
      (node (ref "C12") (pin "1") (pinfunction "P$1_1") (pintype "passive"))
      (node (ref "C2") (pin "1") (pinfunction "P$1_1") (pintype "passive"))
      (node (ref "C3") (pin "1") (pinfunction "P$1_1") (pintype "passive"))
      (node (ref "C4") (pin "1") (pinfunction "P$1_1") (pintype "passive"))
      (node (ref "C40") (pin "1") (pinfunction "P$1_1") (pintype "passive"))
      (node (ref "C41") (pin "1") (pinfunction "P$1_1") (pintype "passive"))
      (node (ref "C45") (pin "1") (pinfunction "P$1_1") (pintype "passive"))
      (node (ref "C46") (pin "1") (pinfunction "P$1_1") (pintype "passive"))
      (node (ref "C47") (pin "1") (pinfunction "P$1_1") (pintype "passive"))
      (node (ref "C48") (pin "1") (pinfunction "P$1_1") (pintype "passive"))
      (node (ref "C49") (pin "1") (pinfunction "P$1_1") (pintype "passive"))
      (node (ref "C50") (pin "1") (pinfunction "P$1_1") (pintype "passive"))
      (node (ref "C51") (pin "1") (pinfunction "P$1_1") (pintype "passive"))
      (node (ref "C52") (pin "1") (pinfunction "P$1_1") (pintype "passive"))
      (node (ref "C53") (pin "1") (pinfunction "P$1_1") (pintype "passive"))
      (node (ref "C54") (pin "1") (pinfunction "P$1_1") (pintype "passive"))
      (node (ref "C55") (pin "1") (pinfunction "P$1_1") (pintype "passive"))
      (node (ref "C6") (pin "1") (pinfunction "P$1_1") (pintype "passive"))
      (node (ref "R1") (pin "1") (pinfunction "1_1") (pintype "passive"))
      (node (ref "R3") (pin "2") (pinfunction "2_2") (pintype "passive"))
      (node (ref "S2") (pin "2") (pinfunction "P$2_2") (pintype "bidirectional"))
      (node (ref "U1") (pin "8") (pinfunction "V+_8") (pintype "power_in"))
      (node (ref "U11") (pin "2") (pinfunction "VDD_2") (pintype "power_in"))
      (node (ref "U12") (pin "4") (pinfunction "V+_4") (pintype "power_in"))
      (node (ref "U13") (pin "2") (pinfunction "VDD_2") (pintype "power_in"))
      (node (ref "U14") (pin "4") (pinfunction "V+_4") (pintype "power_in"))
      (node (ref "U15") (pin "4") (pinfunction "V+_4") (pintype "power_in"))
    )
    (net (code "4") (name "5VD") (class "Default")
      (node (ref "C11") (pin "1") (pinfunction "P$1_1") (pintype "passive"))
      (node (ref "C31") (pin "1") (pinfunction "P$1_1") (pintype "passive"))
      (node (ref "C32") (pin "1") (pinfunction "P$1_1") (pintype "passive"))
      (node (ref "C33") (pin "1") (pinfunction "P$1_1") (pintype "passive"))
      (node (ref "C34") (pin "1") (pinfunction "P$1_1") (pintype "passive"))
      (node (ref "C35") (pin "1") (pinfunction "P$1_1") (pintype "passive"))
      (node (ref "C36") (pin "1") (pinfunction "P$1_1") (pintype "passive"))
      (node (ref "C37") (pin "1") (pinfunction "P$1_1") (pintype "passive"))
      (node (ref "C38") (pin "1") (pinfunction "P$1_1") (pintype "passive"))
      (node (ref "C39") (pin "1") (pinfunction "P$1_1") (pintype "passive"))
      (node (ref "R12") (pin "2") (pinfunction "2_2") (pintype "passive"))
      (node (ref "R13") (pin "2") (pinfunction "2_2") (pintype "passive"))
      (node (ref "R14") (pin "2") (pinfunction "2_2") (pintype "passive"))
      (node (ref "R15") (pin "2") (pinfunction "2_2") (pintype "passive"))
      (node (ref "R16") (pin "2") (pinfunction "2_2") (pintype "passive"))
      (node (ref "R17") (pin "2") (pinfunction "2_2") (pintype "passive"))
      (node (ref "R18") (pin "2") (pinfunction "2_2") (pintype "passive"))
      (node (ref "R19") (pin "2") (pinfunction "2_2") (pintype "passive"))
      (node (ref "R2") (pin "2") (pinfunction "2_2") (pintype "passive"))
      (node (ref "R20") (pin "2") (pinfunction "2_2") (pintype "passive"))
      (node (ref "R21") (pin "2") (pinfunction "2_2") (pintype "passive"))
      (node (ref "R22") (pin "2") (pinfunction "2_2") (pintype "passive"))
      (node (ref "R23") (pin "2") (pinfunction "2_2") (pintype "passive"))
      (node (ref "R24") (pin "2") (pinfunction "2_2") (pintype "passive"))
      (node (ref "R25") (pin "2") (pinfunction "2_2") (pintype "passive"))
      (node (ref "R26") (pin "2") (pinfunction "2_2") (pintype "passive"))
      (node (ref "R27") (pin "2") (pinfunction "2_2") (pintype "passive"))
      (node (ref "R28") (pin "2") (pinfunction "2_2") (pintype "passive"))
      (node (ref "R29") (pin "2") (pinfunction "2_2") (pintype "passive"))
      (node (ref "R30") (pin "2") (pinfunction "2_2") (pintype "passive"))
      (node (ref "R31") (pin "2") (pinfunction "2_2") (pintype "passive"))
      (node (ref "S1") (pin "2") (pinfunction "P$2_2") (pintype "bidirectional"))
      (node (ref "U10") (pin "9") (pinfunction "COM_9") (pintype "bidirectional"))
      (node (ref "U5") (pin "16") (pinfunction "VCC_16") (pintype "power_in"))
      (node (ref "U6") (pin "16") (pinfunction "VCC_16") (pintype "power_in"))
      (node (ref "U7") (pin "16") (pinfunction "VCC_16") (pintype "power_in"))
      (node (ref "U8") (pin "9") (pinfunction "COM_9") (pintype "bidirectional"))
      (node (ref "U9") (pin "9") (pinfunction "COM_9") (pintype "bidirectional"))
    )
    (net (code "5") (name "ADCCE") (class "Default")
      (node (ref "U14") (pin "8") (pinfunction "OUT_8") (pintype "output"))
      (node (ref "U14") (pin "9") (pinfunction "-IN_9") (pintype "input"))
      (node (ref "U3") (pin "17") (pinfunction "PTB1_17") (pintype "bidirectional"))
    )
    (net (code "6") (name "ADCCM") (class "Default")
      (node (ref "R10") (pin "2") (pinfunction "2_2") (pintype "passive"))
      (node (ref "R9") (pin "2") (pinfunction "2_2") (pintype "passive"))
      (node (ref "U15") (pin "1") (pinfunction "OUT_1") (pintype "output"))
      (node (ref "U15") (pin "2") (pinfunction "-IN_2") (pintype "input"))
    )
    (net (code "7") (name "ADCCM12") (class "Default")
      (node (ref "R10") (pin "1") (pinfunction "1_1") (pintype "passive"))
      (node (ref "U3") (pin "7") (pinfunction "PTA19_7") (pintype "bidirectional"))
    )
    (net (code "8") (name "ADCCM16") (class "Default")
      (node (ref "R9") (pin "1") (pinfunction "1_1") (pintype "passive"))
      (node (ref "U3") (pin "24") (pinfunction "ADC0_DP0_24") (pintype "bidirectional"))
    )
    (net (code "9") (name "ADCDAC") (class "Default")
      (node (ref "U12") (pin "6") (pinfunction "-IN_6") (pintype "input"))
      (node (ref "U12") (pin "7") (pinfunction "OUT_7") (pintype "output"))
      (node (ref "U3") (pin "18") (pinfunction "PTB2_18") (pintype "bidirectional"))
    )
    (net (code "10") (name "ADCWE") (class "Default")
      (node (ref "U14") (pin "1") (pinfunction "OUT_1") (pintype "output"))
      (node (ref "U14") (pin "2") (pinfunction "-IN_2") (pintype "input"))
      (node (ref "U3") (pin "19") (pinfunction "PTB3_19") (pintype "bidirectional"))
    )
    (net (code "11") (name "AEE") (class "Default")
      (node (ref "P2") (pin "5") (pinfunction "P5_5") (pintype "passive"))
      (node (ref "RL1") (pin "2") (pinfunction "2_2") (pintype "bidirectional"))
    )
    (net (code "12") (name "AGND") (class "Default")
      (node (ref "C10") (pin "2") (pinfunction "P$2_2") (pintype "passive"))
      (node (ref "C12") (pin "2") (pinfunction "P$2_2") (pintype "passive"))
      (node (ref "C17") (pin "2") (pinfunction "P$2_2") (pintype "passive"))
      (node (ref "C19") (pin "2") (pinfunction "P$2_2") (pintype "passive"))
      (node (ref "C2") (pin "2") (pinfunction "P$2_2") (pintype "passive"))
      (node (ref "C21") (pin "2") (pinfunction "P$2_2") (pintype "passive"))
      (node (ref "C22") (pin "2") (pinfunction "P$2_2") (pintype "passive"))
      (node (ref "C27") (pin "2") (pinfunction "P$2_2") (pintype "passive"))
      (node (ref "C3") (pin "2") (pinfunction "P$2_2") (pintype "passive"))
      (node (ref "C4") (pin "2") (pinfunction "P$2_2") (pintype "passive"))
      (node (ref "C40") (pin "2") (pinfunction "P$2_2") (pintype "passive"))
      (node (ref "C41") (pin "2") (pinfunction "P$2_2") (pintype "passive"))
      (node (ref "C45") (pin "2") (pinfunction "P$2_2") (pintype "passive"))
      (node (ref "C46") (pin "2") (pinfunction "P$2_2") (pintype "passive"))
      (node (ref "C47") (pin "2") (pinfunction "P$2_2") (pintype "passive"))
      (node (ref "C48") (pin "2") (pinfunction "P$2_2") (pintype "passive"))
      (node (ref "C49") (pin "2") (pinfunction "P$2_2") (pintype "passive"))
      (node (ref "C50") (pin "2") (pinfunction "P$2_2") (pintype "passive"))
      (node (ref "C51") (pin "2") (pinfunction "P$2_2") (pintype "passive"))
      (node (ref "C52") (pin "2") (pinfunction "P$2_2") (pintype "passive"))
      (node (ref "C53") (pin "2") (pinfunction "P$2_2") (pintype "passive"))
      (node (ref "C54") (pin "2") (pinfunction "P$2_2") (pintype "passive"))
      (node (ref "C55") (pin "2") (pinfunction "P$2_2") (pintype "passive"))
      (node (ref "C6") (pin "2") (pinfunction "P$2_2") (pintype "passive"))
      (node (ref "C7") (pin "2") (pinfunction "P$2_2") (pintype "passive"))
      (node (ref "JP2") (pin "1") (pinfunction "1_1") (pintype "passive"))
      (node (ref "P2") (pin "SH1") (pinfunction "SHIELD_SH1") (pintype "passive"))
      (node (ref "P2") (pin "SH2") (pinfunction "SHIELD_SH2") (pintype "passive"))
      (node (ref "PS1") (pin "2") (pinfunction "ANODE_2") (pintype "bidirectional"))
      (node (ref "PS3") (pin "1") (pinfunction "GND_1") (pintype "bidirectional"))
      (node (ref "R32") (pin "1") (pinfunction "1_1") (pintype "passive"))
      (node (ref "R4") (pin "2") (pinfunction "2_2") (pintype "passive"))
      (node (ref "R40") (pin "1") (pinfunction "1_1") (pintype "passive"))
      (node (ref "R42") (pin "1") (pinfunction "1_1") (pintype "passive"))
      (node (ref "R44") (pin "1") (pinfunction "1_1") (pintype "passive"))
      (node (ref "U1") (pin "4") (pinfunction "V-_4") (pintype "power_in"))
      (node (ref "U11") (pin "3") (pinfunction "GND_3") (pintype "power_in"))
      (node (ref "U12") (pin "11") (pinfunction "V-_11") (pintype "power_in"))
      (node (ref "U13") (pin "3") (pinfunction "GND_3") (pintype "power_in"))
      (node (ref "U14") (pin "11") (pinfunction "V-_11") (pintype "power_in"))
      (node (ref "U15") (pin "11") (pinfunction "V-_11") (pintype "power_in"))
      (node (ref "U3") (pin "25") (pinfunction "ADC0_DM0_25") (pintype "bidirectional"))
      (node (ref "U3") (pin "26") (pinfunction "VSSA_26") (pintype "power_in"))
      (node (ref "U4") (pin "2") (pinfunction "V-_2") (pintype "power_in"))
    )
    (net (code "13") (name "CD1E") (class "Default")
      (node (ref "U3") (pin "16") (pinfunction "PTB0_16") (pintype "bidirectional"))
      (node (ref "U5") (pin "6") (pinfunction "E3_6") (pintype "bidirectional"))
    )
    (net (code "14") (name "CD2E") (class "Default")
      (node (ref "U3") (pin "37") (pinfunction "PTC1_37") (pintype "bidirectional"))
      (node (ref "U6") (pin "6") (pinfunction "E3_6") (pintype "bidirectional"))
    )
    (net (code "15") (name "CD3E") (class "Default")
      (node (ref "U3") (pin "42") (pinfunction "PTC6_42") (pintype "bidirectional"))
      (node (ref "U7") (pin "6") (pinfunction "E3_6") (pintype "bidirectional"))
    )
    (net (code "16") (name "CD10") (class "Default")
      (node (ref "U3") (pin "4") (pinfunction "PTA16_4") (pintype "bidirectional"))
      (node (ref "U5") (pin "1") (pinfunction "A0_1") (pintype "bidirectional"))
    )
    (net (code "17") (name "CD11") (class "Default")
      (node (ref "U3") (pin "5") (pinfunction "PTA17_5") (pintype "bidirectional"))
      (node (ref "U5") (pin "2") (pinfunction "A1_2") (pintype "bidirectional"))
    )
    (net (code "18") (name "CD12") (class "Default")
      (node (ref "U3") (pin "6") (pinfunction "PTA18_6") (pintype "bidirectional"))
      (node (ref "U5") (pin "3") (pinfunction "A2_3") (pintype "bidirectional"))
    )
    (net (code "19") (name "CD20") (class "Default")
      (node (ref "U3") (pin "40") (pinfunction "PTC4_40") (pintype "bidirectional"))
      (node (ref "U6") (pin "1") (pinfunction "A0_1") (pintype "bidirectional"))
    )
    (net (code "20") (name "CD21") (class "Default")
      (node (ref "U3") (pin "39") (pinfunction "PTC3_39") (pintype "bidirectional"))
      (node (ref "U6") (pin "2") (pinfunction "A1_2") (pintype "bidirectional"))
    )
    (net (code "21") (name "CD22") (class "Default")
      (node (ref "U3") (pin "38") (pinfunction "PTC2_38") (pintype "bidirectional"))
      (node (ref "U6") (pin "3") (pinfunction "A2_3") (pintype "bidirectional"))
    )
    (net (code "22") (name "CD30") (class "Default")
      (node (ref "U3") (pin "21") (pinfunction "PTB16_21") (pintype "bidirectional"))
      (node (ref "U7") (pin "1") (pinfunction "A0_1") (pintype "bidirectional"))
    )
    (net (code "23") (name "CD31") (class "Default")
      (node (ref "U3") (pin "22") (pinfunction "PTB17_22") (pintype "bidirectional"))
      (node (ref "U7") (pin "2") (pinfunction "A1_2") (pintype "bidirectional"))
    )
    (net (code "24") (name "CD32") (class "Default")
      (node (ref "U3") (pin "43") (pinfunction "PTC7_43") (pintype "bidirectional"))
      (node (ref "U7") (pin "3") (pinfunction "A2_3") (pintype "bidirectional"))
    )
    (net (code "25") (name "CE") (class "Default")
      (node (ref "P2") (pin "4") (pinfunction "P4_4") (pintype "passive"))
      (node (ref "RL5") (pin "6") (pinfunction "6_6") (pintype "bidirectional"))
    )
    (net (code "26") (name "CI1") (class "Default")
      (node (ref "R36") (pin "2") (pinfunction "2_2") (pintype "passive"))
      (node (ref "RL9") (pin "2") (pinfunction "2_2") (pintype "bidirectional"))
      (node (ref "U15") (pin "9") (pinfunction "-IN_9") (pintype "input"))
    )
    (net (code "27") (name "CI2") (class "Default")
      (node (ref "CI") (pin "P$1") (pinfunction "P$1_P$1") (pintype "bidirectional"))
      (node (ref "RL10") (pin "2") (pinfunction "2_2") (pintype "bidirectional"))
      (node (ref "RL9") (pin "7") (pinfunction "7_7") (pintype "bidirectional"))
      (node (ref "U15") (pin "8") (pinfunction "OUT_8") (pintype "output"))
    )
    (net (code "28") (name "CII") (class "Default")
      (node (ref "R36") (pin "1") (pinfunction "1_1") (pintype "passive"))
      (node (ref "RL2") (pin "3") (pinfunction "3_3") (pintype "bidirectional"))
      (node (ref "RL9") (pin "4") (pinfunction "4_4") (pintype "bidirectional"))
    )
    (net (code "29") (name "CMI") (class "Default")
      (node (ref "C44") (pin "1") (pinfunction "P$1_1") (pintype "passive"))
      (node (ref "RL4") (pin "4") (pinfunction "4_4") (pintype "bidirectional"))
      (node (ref "U11") (pin "5") (pinfunction "D_5") (pintype "bidirectional"))
      (node (ref "U15") (pin "13") (pinfunction "-IN_13") (pintype "input"))
    )
    (net (code "30") (name "DAC") (class "Default")
      (node (ref "U12") (pin "12") (pinfunction "+IN_12") (pintype "input"))
      (node (ref "U12") (pin "5") (pinfunction "+IN_5") (pintype "input"))
      (node (ref "U3") (pin "23") (pinfunction "PTB18_23") (pintype "bidirectional"))
    )
    (net (code "31") (name "DAC5V") (class "Default")
      (node (ref "R37") (pin "2") (pinfunction "2_2") (pintype "passive"))
      (node (ref "R38") (pin "2") (pinfunction "2_2") (pintype "passive"))
      (node (ref "RL8") (pin "3") (pinfunction "3_3") (pintype "bidirectional"))
    )
    (net (code "32") (name "DAC5V_PRE0AS") (class "Default")
      (node (ref "DAC") (pin "P$1") (pinfunction "P$1_P$1") (pintype "bidirectional"))
      (node (ref "R33") (pin "2") (pinfunction "2_2") (pintype "passive"))
      (node (ref "R37") (pin "1") (pinfunction "1_1") (pintype "passive"))
      (node (ref "U12") (pin "14") (pinfunction "OUT_14") (pintype "output"))
      (node (ref "U13") (pin "4") (pinfunction "S1_4") (pintype "bidirectional"))
    )
    (net (code "33") (name "DACCE") (class "Default")
      (node (ref "R45") (pin "1") (pinfunction "1_1") (pintype "passive"))
      (node (ref "RL8") (pin "4") (pinfunction "4_4") (pintype "bidirectional"))
    )
    (net (code "34") (name "DACGRD") (class "Default")
      (node (ref "RL2") (pin "2") (pinfunction "2_2") (pintype "bidirectional"))
      (node (ref "RL8") (pin "2") (pinfunction "2_2") (pintype "bidirectional"))
    )
    (net (code "35") (name "DGND") (class "Default")
      (node (ref "AE1") (pin "GNDB") (pinfunction "GND_GNDB") (pintype "bidirectional"))
      (node (ref "AE1") (pin "GNDT") (pinfunction "GND_GNDT") (pintype "bidirectional"))
      (node (ref "C1") (pin "2") (pinfunction "2_2") (pintype "bidirectional"))
      (node (ref "C11") (pin "2") (pinfunction "P$2_2") (pintype "passive"))
      (node (ref "C13") (pin "2") (pinfunction "P$2_2") (pintype "passive"))
      (node (ref "C14") (pin "2") (pinfunction "P$2_2") (pintype "passive"))
      (node (ref "C15") (pin "2") (pinfunction "P$2_2") (pintype "passive"))
      (node (ref "C16") (pin "2") (pinfunction "P$2_2") (pintype "passive"))
      (node (ref "C18") (pin "2") (pinfunction "P$2_2") (pintype "passive"))
      (node (ref "C20") (pin "2") (pinfunction "P$2_2") (pintype "passive"))
      (node (ref "C23") (pin "2") (pinfunction "P$2_2") (pintype "passive"))
      (node (ref "C24") (pin "2") (pinfunction "P$2_2") (pintype "passive"))
      (node (ref "C25") (pin "2") (pinfunction "P$2_2") (pintype "passive"))
      (node (ref "C26") (pin "2") (pinfunction "P$2_2") (pintype "passive"))
      (node (ref "C28") (pin "2") (pinfunction "P$2_2") (pintype "passive"))
      (node (ref "C30") (pin "2") (pinfunction "P$2_2") (pintype "passive"))
      (node (ref "C31") (pin "2") (pinfunction "P$2_2") (pintype "passive"))
      (node (ref "C32") (pin "2") (pinfunction "P$2_2") (pintype "passive"))
      (node (ref "C33") (pin "2") (pinfunction "P$2_2") (pintype "passive"))
      (node (ref "C34") (pin "2") (pinfunction "P$2_2") (pintype "passive"))
      (node (ref "C35") (pin "2") (pinfunction "P$2_2") (pintype "passive"))
      (node (ref "C36") (pin "2") (pinfunction "P$2_2") (pintype "passive"))
      (node (ref "C37") (pin "2") (pinfunction "P$2_2") (pintype "passive"))
      (node (ref "C38") (pin "2") (pinfunction "P$2_2") (pintype "passive"))
      (node (ref "C39") (pin "2") (pinfunction "P$2_2") (pintype "passive"))
      (node (ref "C5") (pin "2") (pinfunction "2_2") (pintype "bidirectional"))
      (node (ref "C8") (pin "2") (pinfunction "P$2_2") (pintype "passive"))
      (node (ref "C9") (pin "2") (pinfunction "P$2_2") (pintype "passive"))
      (node (ref "J1") (pin "2") (pinfunction "2_2") (pintype "passive"))
      (node (ref "J2") (pin "3") (pinfunction "3_3") (pintype "bidirectional"))
      (node (ref "J2") (pin "5") (pinfunction "5_5") (pintype "bidirectional"))
      (node (ref "PS2") (pin "1") (pinfunction "GND_1") (pintype "bidirectional"))
      (node (ref "PS4") (pin "2") (pinfunction "GND_2") (pintype "bidirectional"))
      (node (ref "PS5") (pin "2") (pinfunction "GND_2") (pintype "bidirectional"))
      (node (ref "R4") (pin "1") (pinfunction "1_1") (pintype "passive"))
      (node (ref "R8") (pin "1") (pinfunction "1_1") (pintype "passive"))
      (node (ref "U10") (pin "7") (pinfunction "IN7_7") (pintype "input"))
      (node (ref "U10") (pin "8") (pinfunction "GND_8") (pintype "power_in"))
      (node (ref "U2") (pin "4") (pinfunction "GND_4") (pintype "power_in"))
      (node (ref "U3") (pin "13") (pinfunction "DCDC_GND_13") (pintype "bidirectional"))
      (node (ref "U3") (pin "34") (pinfunction "GANT_34") (pintype "bidirectional"))
      (node (ref "U3") (pin "49") (pinfunction "DCDC_GND_49") (pintype "bidirectional"))
      (node (ref "U3") (pin "50") (pinfunction "DCDC_GND_50") (pintype "bidirectional"))
      (node (ref "U3") (pin "51") (pinfunction "DCDC_GND_51") (pintype "bidirectional"))
      (node (ref "U3") (pin "52") (pinfunction "DCDC_GND_52") (pintype "bidirectional"))
      (node (ref "U3") (pin "53") (pinfunction "DCDC_GND_53") (pintype "bidirectional"))
      (node (ref "U3") (pin "54") (pinfunction "DCDC_GND_54") (pintype "bidirectional"))
      (node (ref "U3") (pin "55") (pinfunction "DCDC_GND_55") (pintype "bidirectional"))
      (node (ref "U3") (pin "56") (pinfunction "DCDC_GND_56") (pintype "bidirectional"))
      (node (ref "U3") (pin "57") (pinfunction "DCDC_GND_57") (pintype "bidirectional"))
      (node (ref "U3") (pin "58") (pinfunction "DCDC_GND_58") (pintype "bidirectional"))
      (node (ref "U3") (pin "59") (pinfunction "DCDC_GND_59") (pintype "bidirectional"))
      (node (ref "U3") (pin "60") (pinfunction "DCDC_GND_60") (pintype "bidirectional"))
      (node (ref "U3") (pin "61") (pinfunction "DCDC_GND_61") (pintype "bidirectional"))
      (node (ref "U3") (pin "62") (pinfunction "DCDC_GND_62") (pintype "bidirectional"))
      (node (ref "U3") (pin "63") (pinfunction "DCDC_GND_63") (pintype "bidirectional"))
      (node (ref "U3") (pin "64") (pinfunction "DCDC_GND_64") (pintype "bidirectional"))
      (node (ref "U3") (pin "8") (pinfunction "PSWITCH_8") (pintype "bidirectional"))
      (node (ref "U5") (pin "4") (pinfunction "~{E1}_4") (pintype "bidirectional"))
      (node (ref "U5") (pin "5") (pinfunction "~{E2}_5") (pintype "bidirectional"))
      (node (ref "U5") (pin "8") (pinfunction "GND_8") (pintype "power_in"))
      (node (ref "U6") (pin "4") (pinfunction "~{E1}_4") (pintype "bidirectional"))
      (node (ref "U6") (pin "5") (pinfunction "~{E2}_5") (pintype "bidirectional"))
      (node (ref "U6") (pin "8") (pinfunction "GND_8") (pintype "power_in"))
      (node (ref "U7") (pin "4") (pinfunction "~{E1}_4") (pintype "bidirectional"))
      (node (ref "U7") (pin "5") (pinfunction "~{E2}_5") (pintype "bidirectional"))
      (node (ref "U7") (pin "8") (pinfunction "GND_8") (pintype "power_in"))
      (node (ref "U8") (pin "8") (pinfunction "GND_8") (pintype "power_in"))
      (node (ref "U9") (pin "8") (pinfunction "GND_8") (pintype "power_in"))
      (node (ref "Y1") (pin "2") (pinfunction "NC_1_2") (pintype "bidirectional"))
      (node (ref "Y1") (pin "4") (pinfunction "NC_2_4") (pintype "bidirectional"))
    )
    (net (code "36") (name "DRV1+") (class "Default")
      (node (ref "R12") (pin "1") (pinfunction "1_1") (pintype "passive"))
      (node (ref "RL1") (pin "1") (pinfunction "L+_1") (pintype "bidirectional"))
      (node (ref "U8") (pin "16") (pinfunction "OUT1_16") (pintype "output"))
    )
    (net (code "37") (name "DRV1-") (class "Default")
      (node (ref "R13") (pin "1") (pinfunction "1_1") (pintype "passive"))
      (node (ref "RL1") (pin "8") (pinfunction "L-_8") (pintype "bidirectional"))
      (node (ref "U8") (pin "15") (pinfunction "OUT2_15") (pintype "output"))
    )
    (net (code "38") (name "DRV2+") (class "Default")
      (node (ref "R14") (pin "1") (pinfunction "1_1") (pintype "passive"))
      (node (ref "RL2") (pin "1") (pinfunction "L+_1") (pintype "bidirectional"))
      (node (ref "U8") (pin "14") (pinfunction "OUT3_14") (pintype "output"))
    )
    (net (code "39") (name "DRV2-") (class "Default")
      (node (ref "R15") (pin "1") (pinfunction "1_1") (pintype "passive"))
      (node (ref "RL2") (pin "8") (pinfunction "L-_8") (pintype "bidirectional"))
      (node (ref "U8") (pin "13") (pinfunction "OUT4_13") (pintype "output"))
    )
    (net (code "40") (name "DRV3+") (class "Default")
      (node (ref "R16") (pin "1") (pinfunction "1_1") (pintype "passive"))
      (node (ref "RL3") (pin "1") (pinfunction "L+_1") (pintype "bidirectional"))
      (node (ref "U8") (pin "12") (pinfunction "OUT5_12") (pintype "output"))
    )
    (net (code "41") (name "DRV3-") (class "Default")
      (node (ref "R17") (pin "1") (pinfunction "1_1") (pintype "passive"))
      (node (ref "RL3") (pin "8") (pinfunction "L-_8") (pintype "bidirectional"))
      (node (ref "U8") (pin "11") (pinfunction "OUT6_11") (pintype "output"))
    )
    (net (code "42") (name "DRV4+") (class "Default")
      (node (ref "R18") (pin "1") (pinfunction "1_1") (pintype "passive"))
      (node (ref "RL4") (pin "1") (pinfunction "L+_1") (pintype "bidirectional"))
      (node (ref "U8") (pin "10") (pinfunction "OUT7_10") (pintype "output"))
    )
    (net (code "43") (name "DRV4-") (class "Default")
      (node (ref "R19") (pin "1") (pinfunction "1_1") (pintype "passive"))
      (node (ref "RL4") (pin "8") (pinfunction "L-_8") (pintype "bidirectional"))
      (node (ref "U9") (pin "16") (pinfunction "OUT1_16") (pintype "output"))
    )
    (net (code "44") (name "DRV5+") (class "Default")
      (node (ref "R20") (pin "1") (pinfunction "1_1") (pintype "passive"))
      (node (ref "RL5") (pin "1") (pinfunction "L+_1") (pintype "bidirectional"))
      (node (ref "U9") (pin "15") (pinfunction "OUT2_15") (pintype "output"))
    )
    (net (code "45") (name "DRV5-") (class "Default")
      (node (ref "R21") (pin "1") (pinfunction "1_1") (pintype "passive"))
      (node (ref "RL5") (pin "8") (pinfunction "L-_8") (pintype "bidirectional"))
      (node (ref "U9") (pin "14") (pinfunction "OUT3_14") (pintype "output"))
    )
    (net (code "46") (name "DRV6+") (class "Default")
      (node (ref "R22") (pin "1") (pinfunction "1_1") (pintype "passive"))
      (node (ref "RL6") (pin "1") (pinfunction "L+_1") (pintype "bidirectional"))
      (node (ref "U9") (pin "13") (pinfunction "OUT4_13") (pintype "output"))
    )
    (net (code "47") (name "DRV6-") (class "Default")
      (node (ref "R23") (pin "1") (pinfunction "1_1") (pintype "passive"))
      (node (ref "RL6") (pin "8") (pinfunction "L-_8") (pintype "bidirectional"))
      (node (ref "U9") (pin "12") (pinfunction "OUT5_12") (pintype "output"))
    )
    (net (code "48") (name "DRV7+") (class "Default")
      (node (ref "R24") (pin "1") (pinfunction "1_1") (pintype "passive"))
      (node (ref "RL7") (pin "1") (pinfunction "L+_1") (pintype "bidirectional"))
      (node (ref "U9") (pin "11") (pinfunction "OUT6_11") (pintype "output"))
    )
    (net (code "49") (name "DRV7-") (class "Default")
      (node (ref "R25") (pin "1") (pinfunction "1_1") (pintype "passive"))
      (node (ref "RL7") (pin "8") (pinfunction "L-_8") (pintype "bidirectional"))
      (node (ref "U9") (pin "10") (pinfunction "OUT7_10") (pintype "output"))
    )
    (net (code "50") (name "DRV8+") (class "Default")
      (node (ref "R26") (pin "1") (pinfunction "1_1") (pintype "passive"))
      (node (ref "RL8") (pin "1") (pinfunction "L+_1") (pintype "bidirectional"))
      (node (ref "U10") (pin "16") (pinfunction "OUT1_16") (pintype "output"))
    )
    (net (code "51") (name "DRV8-") (class "Default")
      (node (ref "R27") (pin "1") (pinfunction "1_1") (pintype "passive"))
      (node (ref "RL8") (pin "8") (pinfunction "L-_8") (pintype "bidirectional"))
      (node (ref "U10") (pin "15") (pinfunction "OUT2_15") (pintype "output"))
    )
    (net (code "52") (name "DRV9+") (class "Default")
      (node (ref "R28") (pin "1") (pinfunction "1_1") (pintype "passive"))
      (node (ref "RL9") (pin "1") (pinfunction "L+_1") (pintype "bidirectional"))
      (node (ref "U10") (pin "14") (pinfunction "OUT3_14") (pintype "output"))
    )
    (net (code "53") (name "DRV9-") (class "Default")
      (node (ref "R29") (pin "1") (pinfunction "1_1") (pintype "passive"))
      (node (ref "RL9") (pin "8") (pinfunction "L-_8") (pintype "bidirectional"))
      (node (ref "U10") (pin "13") (pinfunction "OUT4_13") (pintype "output"))
    )
    (net (code "54") (name "DRV10+") (class "Default")
      (node (ref "R30") (pin "1") (pinfunction "1_1") (pintype "passive"))
      (node (ref "RL10") (pin "1") (pinfunction "L+_1") (pintype "bidirectional"))
      (node (ref "U10") (pin "12") (pinfunction "OUT5_12") (pintype "output"))
    )
    (net (code "55") (name "DRV10-") (class "Default")
      (node (ref "R31") (pin "1") (pinfunction "1_1") (pintype "passive"))
      (node (ref "RL10") (pin "8") (pinfunction "L-_8") (pintype "bidirectional"))
      (node (ref "U10") (pin "11") (pinfunction "OUT6_11") (pintype "output"))
    )
    (net (code "56") (name "FILTERED_VBAT") (class "Default")
      (node (ref "C13") (pin "1") (pinfunction "P$1_1") (pintype "passive"))
      (node (ref "C14") (pin "1") (pinfunction "P$1_1") (pintype "passive"))
      (node (ref "C5") (pin "1") (pinfunction "1_1") (pintype "bidirectional"))
      (node (ref "C8") (pin "1") (pinfunction "P$1_1") (pintype "passive"))
      (node (ref "C9") (pin "1") (pinfunction "P$1_1") (pintype "passive"))
      (node (ref "L1") (pin "1") (pinfunction "1_1") (pintype "passive"))
      (node (ref "PS2") (pin "3") (pinfunction "VIN_3") (pintype "bidirectional"))
      (node (ref "PS3") (pin "3") (pinfunction "VIN_3") (pintype "bidirectional"))
      (node (ref "PS4") (pin "1") (pinfunction "IN_1") (pintype "bidirectional"))
      (node (ref "PS4") (pin "3") (pinfunction "EN_3") (pintype "bidirectional"))
      (node (ref "PS5") (pin "1") (pinfunction "IN_1") (pintype "bidirectional"))
      (node (ref "PS5") (pin "3") (pinfunction "EN_3") (pintype "bidirectional"))
    )
    (net (code "57") (name "Net-(C10-P$1)") (class "Default")
      (node (ref "C10") (pin "1") (pinfunction "P$1_1") (pintype "passive"))
      (node (ref "C7") (pin "1") (pinfunction "P$1_1") (pintype "passive"))
      (node (ref "PS1") (pin "1") (pinfunction "CATHODE_1") (pintype "bidirectional"))
      (node (ref "R1") (pin "2") (pinfunction "2_2") (pintype "passive"))
      (node (ref "U1") (pin "3") (pinfunction "+IN_3") (pintype "input"))
      (node (ref "U1") (pin "5") (pinfunction "+IN_5") (pintype "input"))
    )
    (net (code "58") (name "Net-(C16-P$1)") (class "Default")
      (node (ref "C16") (pin "1") (pinfunction "P$1_1") (pintype "passive"))
      (node (ref "PS4") (pin "5") (pinfunction "OUT_5") (pintype "bidirectional"))
      (node (ref "R5") (pin "1") (pinfunction "1_1") (pintype "passive"))
      (node (ref "S3") (pin "1") (pinfunction "P$1_1") (pintype "bidirectional"))
    )
    (net (code "59") (name "Net-(C17-P$1)") (class "Default")
      (node (ref "C17") (pin "1") (pinfunction "P$1_1") (pintype "passive"))
      (node (ref "PS5") (pin "5") (pinfunction "OUT_5") (pintype "bidirectional"))
      (node (ref "R6") (pin "1") (pinfunction "1_1") (pintype "passive"))
      (node (ref "S4") (pin "1") (pinfunction "P$1_1") (pintype "bidirectional"))
    )
    (net (code "60") (name "Net-(C20-P$1)") (class "Default")
      (node (ref "C20") (pin "1") (pinfunction "P$1_1") (pintype "passive"))
      (node (ref "U3") (pin "10") (pinfunction "VDCDC_IN_10") (pintype "bidirectional"))
      (node (ref "U3") (pin "9") (pinfunction "DCDC_CFG_9") (pintype "bidirectional"))
    )
    (net (code "61") (name "Net-(C21-P$1)") (class "Default")
      (node (ref "C21") (pin "1") (pinfunction "P$1_1") (pintype "passive"))
      (node (ref "L2") (pin "1") (pinfunction "1_1") (pintype "passive"))
      (node (ref "U3") (pin "28") (pinfunction "VDDA_28") (pintype "power_in"))
    )
    (net (code "62") (name "Net-(C22-P$1)") (class "Default")
      (node (ref "C22") (pin "1") (pinfunction "P$1_1") (pintype "passive"))
      (node (ref "R11") (pin "1") (pinfunction "1_1") (pintype "passive"))
      (node (ref "U3") (pin "27") (pinfunction "VREFH/VREF_OUT_27") (pintype "power_in"))
      (node (ref "U4") (pin "1") (pinfunction "V+_1") (pintype "power_in"))
    )
    (net (code "63") (name "Net-(C23-P$1)") (class "Default")
      (node (ref "C23") (pin "1") (pinfunction "P$1_1") (pintype "passive"))
      (node (ref "L3") (pin "1") (pinfunction "1_1") (pintype "passive"))
      (node (ref "U3") (pin "33") (pinfunction "ANT_33") (pintype "bidirectional"))
    )
    (net (code "64") (name "Net-(C26-P$1)") (class "Default")
      (node (ref "C26") (pin "1") (pinfunction "P$1_1") (pintype "passive"))
      (node (ref "C29") (pin "1") (pinfunction "P$1_1") (pintype "passive"))
      (node (ref "L3") (pin "2") (pinfunction "2_2") (pintype "passive"))
    )
    (net (code "65") (name "Net-(C29-P$2)") (class "Default")
      (node (ref "AE1") (pin "P$1") (pinfunction "RF_P$1") (pintype "bidirectional"))
      (node (ref "AE1") (pin "RF") (pinfunction "RF_RF") (pintype "bidirectional"))
      (node (ref "C29") (pin "2") (pinfunction "P$2_2") (pintype "passive"))
      (node (ref "C30") (pin "1") (pinfunction "P$1_1") (pintype "passive"))
    )
    (net (code "66") (name "Net-(C42-P$1)") (class "Default")
      (node (ref "C42") (pin "1") (pinfunction "P$1_1") (pintype "passive"))
      (node (ref "R34") (pin "1") (pinfunction "1_1") (pintype "passive"))
      (node (ref "U11") (pin "4") (pinfunction "S1_4") (pintype "bidirectional"))
    )
    (net (code "67") (name "Net-(C42-P$2)") (class "Default")
      (node (ref "C42") (pin "2") (pinfunction "P$2_2") (pintype "passive"))
      (node (ref "C43") (pin "2") (pinfunction "P$2_2") (pintype "passive"))
      (node (ref "C44") (pin "2") (pinfunction "P$2_2") (pintype "passive"))
      (node (ref "R34") (pin "2") (pinfunction "2_2") (pintype "passive"))
      (node (ref "R35") (pin "2") (pinfunction "2_2") (pintype "passive"))
      (node (ref "U15") (pin "14") (pinfunction "OUT_14") (pintype "output"))
      (node (ref "U15") (pin "5") (pinfunction "+IN_5") (pintype "input"))
    )
    (net (code "68") (name "Net-(C43-P$1)") (class "Default")
      (node (ref "C43") (pin "1") (pinfunction "P$1_1") (pintype "passive"))
      (node (ref "R35") (pin "1") (pinfunction "1_1") (pintype "passive"))
      (node (ref "U11") (pin "6") (pinfunction "S2_6") (pintype "bidirectional"))
    )
    (net (code "69") (name "Net-(C56-P$1)") (class "Default")
      (node (ref "C56") (pin "1") (pinfunction "P$1_1") (pintype "passive"))
      (node (ref "R45") (pin "2") (pinfunction "2_2") (pintype "passive"))
      (node (ref "R46") (pin "2") (pinfunction "2_2") (pintype "passive"))
      (node (ref "U12") (pin "2") (pinfunction "-IN_2") (pintype "input"))
    )
    (net (code "70") (name "Net-(D1-PadC)") (class "Default")
      (node (ref "D1") (pin "C") (pinfunction "C_C") (pintype "passive"))
      (node (ref "R8") (pin "2") (pinfunction "2_2") (pintype "passive"))
    )
    (net (code "71") (name "Net-(P1-PIN1)") (class "Default")
      (node (ref "P1") (pin "1") (pinfunction "PIN1_1") (pintype "bidirectional"))
      (node (ref "R7") (pin "2") (pinfunction "2_2") (pintype "passive"))
      (node (ref "U2") (pin "8") (pinfunction "A_8") (pintype "input"))
    )
    (net (code "72") (name "Net-(P1-PIN2)") (class "Default")
      (node (ref "P1") (pin "2") (pinfunction "PIN2_2") (pintype "bidirectional"))
      (node (ref "R7") (pin "1") (pinfunction "1_1") (pintype "passive"))
      (node (ref "U2") (pin "7") (pinfunction "B_7") (pintype "input"))
    )
    (net (code "73") (name "Net-(P1-PIN3)") (class "Default")
      (node (ref "P1") (pin "3") (pinfunction "PIN3_3") (pintype "bidirectional"))
      (node (ref "U2") (pin "6") (pinfunction "Z_6") (pintype "output"))
    )
    (net (code "74") (name "Net-(P1-PIN4)") (class "Default")
      (node (ref "P1") (pin "4") (pinfunction "PIN4_4") (pintype "bidirectional"))
      (node (ref "U2") (pin "5") (pinfunction "Y_5") (pintype "output"))
    )
    (net (code "75") (name "Net-(PS2-VOUT)") (class "Default")
      (node (ref "PS2") (pin "2") (pinfunction "VOUT_2") (pintype "bidirectional"))
      (node (ref "R2") (pin "1") (pinfunction "1_1") (pintype "passive"))
      (node (ref "S1") (pin "1") (pinfunction "P$1_1") (pintype "bidirectional"))
    )
    (net (code "76") (name "Net-(PS3-VOUT)") (class "Default")
      (node (ref "PS3") (pin "2") (pinfunction "VOUT_2") (pintype "bidirectional"))
      (node (ref "R3") (pin "1") (pinfunction "1_1") (pintype "passive"))
      (node (ref "S2") (pin "1") (pinfunction "P$1_1") (pintype "bidirectional"))
    )
    (net (code "77") (name "Net-(R46-Pad1)") (class "Default")
      (node (ref "R46") (pin "1") (pinfunction "1_1") (pintype "passive"))
      (node (ref "RL7") (pin "6") (pinfunction "6_6") (pintype "bidirectional"))
    )
    (net (code "78") (name "Net-(RL1-Pad3)") (class "Default")
      (node (ref "RL1") (pin "3") (pinfunction "3_3") (pintype "bidirectional"))
      (node (ref "RL9") (pin "3") (pinfunction "3_3") (pintype "bidirectional"))
    )
    (net (code "79") (name "Net-(RL1-Pad6)") (class "Default")
      (node (ref "RL1") (pin "6") (pinfunction "6_6") (pintype "bidirectional"))
      (node (ref "RL9") (pin "6") (pinfunction "6_6") (pintype "bidirectional"))
    )
    (net (code "80") (name "Net-(RL2-Pad4)") (class "Default")
      (node (ref "RL2") (pin "4") (pinfunction "4_4") (pintype "bidirectional"))
      (node (ref "RL2") (pin "5") (pinfunction "5_5") (pintype "bidirectional"))
      (node (ref "RL2") (pin "7") (pinfunction "7_7") (pintype "bidirectional"))
      (node (ref "RL3") (pin "2") (pinfunction "2_2") (pintype "bidirectional"))
    )
    (net (code "81") (name "Net-(RL3-Pad3)") (class "Default")
      (node (ref "RL3") (pin "3") (pinfunction "3_3") (pintype "bidirectional"))
      (node (ref "RL4") (pin "3") (pinfunction "3_3") (pintype "bidirectional"))
    )
    (net (code "82") (name "Net-(RL4-Pad6)") (class "Default")
      (node (ref "RL4") (pin "6") (pinfunction "6_6") (pintype "bidirectional"))
      (node (ref "RL6") (pin "5") (pinfunction "5_5") (pintype "bidirectional"))
    )
    (net (code "83") (name "Net-(RL5-Pad7)") (class "Default")
      (node (ref "RL5") (pin "7") (pinfunction "7_7") (pintype "bidirectional"))
      (node (ref "RL6") (pin "6") (pinfunction "6_6") (pintype "bidirectional"))
    )
    (net (code "84") (name "Net-(RL10-Pad3)") (class "Default")
      (node (ref "RL10") (pin "3") (pinfunction "3_3") (pintype "bidirectional"))
      (node (ref "RL2") (pin "6") (pinfunction "6_6") (pintype "bidirectional"))
    )
    (net (code "85") (name "Net-(RL10-Pad4)") (class "Default")
      (node (ref "RL10") (pin "4") (pinfunction "4_4") (pintype "bidirectional"))
      (node (ref "RL9") (pin "5") (pinfunction "5_5") (pintype "bidirectional"))
    )
    (net (code "86") (name "Net-(U3-EXTAL)") (class "Default")
      (node (ref "U3") (pin "30") (pinfunction "EXTAL_30") (pintype "bidirectional"))
      (node (ref "Y1") (pin "3") (pinfunction "CRYSTAL_2_3") (pintype "bidirectional"))
    )
    (net (code "87") (name "Net-(U3-XTAL)") (class "Default")
      (node (ref "U3") (pin "31") (pinfunction "XTAL_31") (pintype "bidirectional"))
      (node (ref "Y1") (pin "1") (pinfunction "CRYSTAL_1_1") (pintype "bidirectional"))
    )
    (net (code "88") (name "Net-(U12C--IN)") (class "Default")
      (node (ref "RL7") (pin "5") (pinfunction "5_5") (pintype "bidirectional"))
      (node (ref "U12") (pin "8") (pinfunction "OUT_8") (pintype "output"))
      (node (ref "U12") (pin "9") (pinfunction "-IN_9") (pintype "input"))
    )
    (net (code "89") (name "Net-(U12D--IN)") (class "Default")
      (node (ref "R32") (pin "2") (pinfunction "2_2") (pintype "passive"))
      (node (ref "R33") (pin "1") (pinfunction "1_1") (pintype "passive"))
      (node (ref "U12") (pin "13") (pinfunction "-IN_13") (pintype "input"))
    )
    (net (code "90") (name "Net-(U13-D)") (class "Default")
      (node (ref "R38") (pin "1") (pinfunction "1_1") (pintype "passive"))
      (node (ref "U13") (pin "5") (pinfunction "D_5") (pintype "bidirectional"))
    )
    (net (code "91") (name "Net-(U14A-+IN)") (class "Default")
      (node (ref "R39") (pin "1") (pinfunction "1_1") (pintype "passive"))
      (node (ref "R40") (pin "2") (pinfunction "2_2") (pintype "passive"))
      (node (ref "U14") (pin "3") (pinfunction "+IN_3") (pintype "input"))
    )
    (net (code "92") (name "Net-(U14B--IN)") (class "Default")
      (node (ref "R39") (pin "2") (pinfunction "2_2") (pintype "passive"))
      (node (ref "U14") (pin "6") (pinfunction "-IN_6") (pintype "input"))
      (node (ref "U14") (pin "7") (pinfunction "OUT_7") (pintype "output"))
      (node (ref "WE") (pin "P$1") (pinfunction "P$1_P$1") (pintype "bidirectional"))
    )
    (net (code "93") (name "Net-(U14C-+IN)") (class "Default")
      (node (ref "R41") (pin "1") (pinfunction "1_1") (pintype "passive"))
      (node (ref "R42") (pin "2") (pinfunction "2_2") (pintype "passive"))
      (node (ref "U14") (pin "10") (pinfunction "+IN_10") (pintype "input"))
    )
    (net (code "94") (name "Net-(U14D--IN)") (class "Default")
      (node (ref "R41") (pin "2") (pinfunction "2_2") (pintype "passive"))
      (node (ref "RE") (pin "P$1") (pinfunction "P$1_P$1") (pintype "bidirectional"))
      (node (ref "U14") (pin "13") (pinfunction "-IN_13") (pintype "input"))
      (node (ref "U14") (pin "14") (pinfunction "OUT_14") (pintype "output"))
    )
    (net (code "95") (name "Net-(U15A-+IN)") (class "Default")
      (node (ref "R43") (pin "1") (pinfunction "1_1") (pintype "passive"))
      (node (ref "R44") (pin "2") (pinfunction "2_2") (pintype "passive"))
      (node (ref "U15") (pin "3") (pinfunction "+IN_3") (pintype "input"))
    )
    (net (code "96") (name "Net-(U15B--IN)") (class "Default")
      (node (ref "CM") (pin "P$1") (pinfunction "P$1_P$1") (pintype "bidirectional"))
      (node (ref "R43") (pin "2") (pinfunction "2_2") (pintype "passive"))
      (node (ref "U15") (pin "6") (pinfunction "-IN_6") (pintype "input"))
      (node (ref "U15") (pin "7") (pinfunction "OUT_7") (pintype "output"))
    )
    (net (code "97") (name "PEE") (class "Default")
      (node (ref "P2") (pin "1") (pinfunction "P1_1") (pintype "passive"))
      (node (ref "RL1") (pin "7") (pinfunction "7_7") (pintype "bidirectional"))
    )
    (net (code "98") (name "POTOUT") (class "Default")
      (node (ref "C56") (pin "2") (pinfunction "P$2_2") (pintype "passive"))
      (node (ref "RL4") (pin "5") (pinfunction "5_5") (pintype "bidirectional"))
      (node (ref "RL7") (pin "7") (pinfunction "7_7") (pintype "bidirectional"))
      (node (ref "U12") (pin "1") (pinfunction "OUT_1") (pintype "output"))
      (node (ref "U14") (pin "12") (pinfunction "+IN_12") (pintype "input"))
    )
    (net (code "99") (name "PREADCWE") (class "Default")
      (node (ref "RL4") (pin "2") (pinfunction "2_2") (pintype "bidirectional"))
      (node (ref "U14") (pin "5") (pinfunction "+IN_5") (pintype "input"))
    )
    (net (code "100") (name "PR_RE") (class "Default")
      (node (ref "RL5") (pin "2") (pinfunction "2_2") (pintype "bidirectional"))
      (node (ref "U12") (pin "10") (pinfunction "+IN_10") (pintype "input"))
    )
    (net (code "101") (name "RE") (class "Default")
      (node (ref "P2") (pin "3") (pinfunction "P3_3") (pintype "passive"))
      (node (ref "RL5") (pin "3") (pinfunction "3_3") (pintype "bidirectional"))
    )
    (net (code "102") (name "RELAY1_1") (class "Default")
      (node (ref "U5") (pin "15") (pinfunction "Y0_15") (pintype "bidirectional"))
      (node (ref "U8") (pin "1") (pinfunction "IN1_1") (pintype "input"))
    )
    (net (code "103") (name "RELAY1_2") (class "Default")
      (node (ref "U5") (pin "14") (pinfunction "Y1_14") (pintype "bidirectional"))
      (node (ref "U8") (pin "2") (pinfunction "IN2_2") (pintype "input"))
    )
    (net (code "104") (name "RELAY2_1") (class "Default")
      (node (ref "U5") (pin "13") (pinfunction "Y2_13") (pintype "bidirectional"))
      (node (ref "U8") (pin "3") (pinfunction "IN3_3") (pintype "input"))
    )
    (net (code "105") (name "RELAY2_2") (class "Default")
      (node (ref "U5") (pin "12") (pinfunction "Y3_12") (pintype "bidirectional"))
      (node (ref "U8") (pin "4") (pinfunction "IN4_4") (pintype "input"))
    )
    (net (code "106") (name "RELAY3_1") (class "Default")
      (node (ref "U5") (pin "11") (pinfunction "Y4_11") (pintype "bidirectional"))
      (node (ref "U8") (pin "5") (pinfunction "IN5_5") (pintype "input"))
    )
    (net (code "107") (name "RELAY3_2") (class "Default")
      (node (ref "U5") (pin "10") (pinfunction "Y5_10") (pintype "bidirectional"))
      (node (ref "U8") (pin "6") (pinfunction "IN6_6") (pintype "input"))
    )
    (net (code "108") (name "RELAY4_1") (class "Default")
      (node (ref "U5") (pin "9") (pinfunction "Y6_9") (pintype "bidirectional"))
      (node (ref "U8") (pin "7") (pinfunction "IN7_7") (pintype "input"))
    )
    (net (code "109") (name "RELAY4_2") (class "Default")
      (node (ref "U5") (pin "7") (pinfunction "Y7_7") (pintype "bidirectional"))
      (node (ref "U9") (pin "1") (pinfunction "IN1_1") (pintype "input"))
    )
    (net (code "110") (name "RELAY5_1") (class "Default")
      (node (ref "U6") (pin "15") (pinfunction "Y0_15") (pintype "bidirectional"))
      (node (ref "U9") (pin "2") (pinfunction "IN2_2") (pintype "input"))
    )
    (net (code "111") (name "RELAY5_2") (class "Default")
      (node (ref "U6") (pin "14") (pinfunction "Y1_14") (pintype "bidirectional"))
      (node (ref "U9") (pin "3") (pinfunction "IN3_3") (pintype "input"))
    )
    (net (code "112") (name "RELAY6_1") (class "Default")
      (node (ref "U6") (pin "13") (pinfunction "Y2_13") (pintype "bidirectional"))
      (node (ref "U9") (pin "4") (pinfunction "IN4_4") (pintype "input"))
    )
    (net (code "113") (name "RELAY6_2") (class "Default")
      (node (ref "U6") (pin "12") (pinfunction "Y3_12") (pintype "bidirectional"))
      (node (ref "U9") (pin "5") (pinfunction "IN5_5") (pintype "input"))
    )
    (net (code "114") (name "RELAY7_1") (class "Default")
      (node (ref "U6") (pin "11") (pinfunction "Y4_11") (pintype "bidirectional"))
      (node (ref "U9") (pin "6") (pinfunction "IN6_6") (pintype "input"))
    )
    (net (code "115") (name "RELAY7_2") (class "Default")
      (node (ref "U6") (pin "10") (pinfunction "Y5_10") (pintype "bidirectional"))
      (node (ref "U9") (pin "7") (pinfunction "IN7_7") (pintype "input"))
    )
    (net (code "116") (name "RELAY8_1") (class "Default")
      (node (ref "U10") (pin "1") (pinfunction "IN1_1") (pintype "input"))
      (node (ref "U6") (pin "9") (pinfunction "Y6_9") (pintype "bidirectional"))
    )
    (net (code "117") (name "RELAY8_2") (class "Default")
      (node (ref "U10") (pin "2") (pinfunction "IN2_2") (pintype "input"))
      (node (ref "U6") (pin "7") (pinfunction "Y7_7") (pintype "bidirectional"))
    )
    (net (code "118") (name "RELAY9_1") (class "Default")
      (node (ref "U10") (pin "3") (pinfunction "IN3_3") (pintype "input"))
      (node (ref "U7") (pin "15") (pinfunction "Y0_15") (pintype "bidirectional"))
    )
    (net (code "119") (name "RELAY9_2") (class "Default")
      (node (ref "U10") (pin "4") (pinfunction "IN4_4") (pintype "input"))
      (node (ref "U7") (pin "14") (pinfunction "Y1_14") (pintype "bidirectional"))
    )
    (net (code "120") (name "RELAY10_1") (class "Default")
      (node (ref "U10") (pin "5") (pinfunction "IN5_5") (pintype "input"))
      (node (ref "U7") (pin "13") (pinfunction "Y2_13") (pintype "bidirectional"))
    )
    (net (code "121") (name "RELAY10_2") (class "Default")
      (node (ref "U10") (pin "6") (pinfunction "IN6_6") (pintype "input"))
      (node (ref "U7") (pin "12") (pinfunction "Y3_12") (pintype "bidirectional"))
    )
    (net (code "122") (name "RST_MCU") (class "Default")
      (node (ref "J2") (pin "10") (pinfunction "10_10") (pintype "bidirectional"))
      (node (ref "U3") (pin "3") (pinfunction "PTA2_3") (pintype "bidirectional"))
    )
    (net (code "123") (name "SEL_SCA") (class "Default")
      (node (ref "U11") (pin "1") (pinfunction "IN_1") (pintype "bidirectional"))
      (node (ref "U3") (pin "41") (pinfunction "PTC5_41") (pintype "bidirectional"))
    )
    (net (code "124") (name "SET0V") (class "Default")
      (node (ref "U13") (pin "1") (pinfunction "IN_1") (pintype "bidirectional"))
      (node (ref "U3") (pin "48") (pinfunction "PTC19_48") (pintype "bidirectional"))
    )
    (net (code "125") (name "SWD_CLK") (class "Default")
      (node (ref "J2") (pin "4") (pinfunction "4_4") (pintype "bidirectional"))
      (node (ref "U3") (pin "2") (pinfunction "PTA1_2") (pintype "bidirectional"))
    )
    (net (code "126") (name "SWD_DIO") (class "Default")
      (node (ref "J2") (pin "2") (pinfunction "2_2") (pintype "bidirectional"))
      (node (ref "U3") (pin "1") (pinfunction "PTA0_1") (pintype "bidirectional"))
    )
    (net (code "127") (name "UART_RX_UC") (class "Default")
      (node (ref "U2") (pin "2") (pinfunction "RO_2") (pintype "output"))
      (node (ref "U3") (pin "46") (pinfunction "PTC17_46") (pintype "bidirectional"))
    )
    (net (code "128") (name "UART_TX_UC") (class "Default")
      (node (ref "U2") (pin "3") (pinfunction "DI_3") (pintype "input"))
      (node (ref "U3") (pin "47") (pinfunction "PTC18_47") (pintype "bidirectional"))
    )
    (net (code "129") (name "VBAT") (class "Default")
      (node (ref "C1") (pin "1") (pinfunction "1_1") (pintype "bidirectional"))
      (node (ref "J1") (pin "1") (pinfunction "1_1") (pintype "passive"))
      (node (ref "L1") (pin "2") (pinfunction "2_2") (pintype "passive"))
    )
    (net (code "130") (name "VGND") (class "Default")
      (node (ref "JP1") (pin "1") (pinfunction "1_1") (pintype "passive"))
      (node (ref "RL5") (pin "4") (pinfunction "4_4") (pintype "bidirectional"))
      (node (ref "U1") (pin "1") (pinfunction "OUT_1") (pintype "output"))
      (node (ref "U1") (pin "2") (pinfunction "-IN_2") (pintype "input"))
      (node (ref "U1") (pin "6") (pinfunction "-IN_6") (pintype "input"))
      (node (ref "U1") (pin "7") (pinfunction "OUT_7") (pintype "output"))
      (node (ref "U12") (pin "3") (pinfunction "+IN_3") (pintype "input"))
      (node (ref "U13") (pin "6") (pinfunction "S2_6") (pintype "bidirectional"))
      (node (ref "U15") (pin "10") (pinfunction "+IN_10") (pintype "input"))
      (node (ref "U15") (pin "12") (pinfunction "+IN_12") (pintype "input"))
    )
    (net (code "131") (name "WE") (class "Default")
      (node (ref "P2") (pin "2") (pinfunction "P2_2") (pintype "passive"))
      (node (ref "RL3") (pin "4") (pinfunction "4_4") (pintype "bidirectional"))
    )
    (net (code "132") (name "unconnected-(J2-Pad6)") (class "Default")
      (node (ref "J2") (pin "6") (pinfunction "6_6") (pintype "bidirectional"))
    )
    (net (code "133") (name "unconnected-(J2-Pad7)") (class "Default")
      (node (ref "J2") (pin "7") (pinfunction "7_7") (pintype "bidirectional"))
    )
    (net (code "134") (name "unconnected-(J2-Pad8)") (class "Default")
      (node (ref "J2") (pin "8") (pinfunction "8_8") (pintype "bidirectional"))
    )
    (net (code "135") (name "unconnected-(J2-Pad9)") (class "Default")
      (node (ref "J2") (pin "9") (pinfunction "9_9") (pintype "bidirectional"))
    )
    (net (code "136") (name "unconnected-(PS1-NC-Pad3)") (class "Default")
      (node (ref "PS1") (pin "3") (pinfunction "NC_3") (pintype "no_connect"))
    )
    (net (code "137") (name "unconnected-(PS4-NC-Pad4)") (class "Default")
      (node (ref "PS4") (pin "4") (pinfunction "NC_4") (pintype "bidirectional"))
    )
    (net (code "138") (name "unconnected-(PS5-NC-Pad4)") (class "Default")
      (node (ref "PS5") (pin "4") (pinfunction "NC_4") (pintype "bidirectional"))
    )
    (net (code "139") (name "unconnected-(RL1-Pad4)") (class "Default")
      (node (ref "RL1") (pin "4") (pinfunction "4_4") (pintype "bidirectional"))
    )
    (net (code "140") (name "unconnected-(RL1-Pad5)") (class "Default")
      (node (ref "RL1") (pin "5") (pinfunction "5_5") (pintype "bidirectional"))
    )
    (net (code "141") (name "unconnected-(RL3-Pad5)") (class "Default")
      (node (ref "RL3") (pin "5") (pinfunction "5_5") (pintype "bidirectional"))
    )
    (net (code "142") (name "unconnected-(RL3-Pad6)") (class "Default")
      (node (ref "RL3") (pin "6") (pinfunction "6_6") (pintype "bidirectional"))
    )
    (net (code "143") (name "unconnected-(RL3-Pad7)") (class "Default")
      (node (ref "RL3") (pin "7") (pinfunction "7_7") (pintype "bidirectional"))
    )
    (net (code "144") (name "unconnected-(RL4-Pad7)") (class "Default")
      (node (ref "RL4") (pin "7") (pinfunction "7_7") (pintype "bidirectional"))
    )
    (net (code "145") (name "unconnected-(RL5-Pad5)") (class "Default")
      (node (ref "RL5") (pin "5") (pinfunction "5_5") (pintype "bidirectional"))
    )
    (net (code "146") (name "unconnected-(RL6-Pad2)") (class "Default")
      (node (ref "RL6") (pin "2") (pinfunction "2_2") (pintype "bidirectional"))
    )
    (net (code "147") (name "unconnected-(RL6-Pad3)") (class "Default")
      (node (ref "RL6") (pin "3") (pinfunction "3_3") (pintype "bidirectional"))
    )
    (net (code "148") (name "unconnected-(RL6-Pad4)") (class "Default")
      (node (ref "RL6") (pin "4") (pinfunction "4_4") (pintype "bidirectional"))
    )
    (net (code "149") (name "unconnected-(RL6-Pad7)") (class "Default")
      (node (ref "RL6") (pin "7") (pinfunction "7_7") (pintype "bidirectional"))
    )
    (net (code "150") (name "unconnected-(RL7-Pad2)") (class "Default")
      (node (ref "RL7") (pin "2") (pinfunction "2_2") (pintype "bidirectional"))
    )
    (net (code "151") (name "unconnected-(RL7-Pad3)") (class "Default")
      (node (ref "RL7") (pin "3") (pinfunction "3_3") (pintype "bidirectional"))
    )
    (net (code "152") (name "unconnected-(RL7-Pad4)") (class "Default")
      (node (ref "RL7") (pin "4") (pinfunction "4_4") (pintype "bidirectional"))
    )
    (net (code "153") (name "unconnected-(RL8-Pad5)") (class "Default")
      (node (ref "RL8") (pin "5") (pinfunction "5_5") (pintype "bidirectional"))
    )
    (net (code "154") (name "unconnected-(RL8-Pad6)") (class "Default")
      (node (ref "RL8") (pin "6") (pinfunction "6_6") (pintype "bidirectional"))
    )
    (net (code "155") (name "unconnected-(RL8-Pad7)") (class "Default")
      (node (ref "RL8") (pin "7") (pinfunction "7_7") (pintype "bidirectional"))
    )
    (net (code "156") (name "unconnected-(RL10-Pad5)") (class "Default")
      (node (ref "RL10") (pin "5") (pinfunction "5_5") (pintype "bidirectional"))
    )
    (net (code "157") (name "unconnected-(RL10-Pad6)") (class "Default")
      (node (ref "RL10") (pin "6") (pinfunction "6_6") (pintype "bidirectional"))
    )
    (net (code "158") (name "unconnected-(RL10-Pad7)") (class "Default")
      (node (ref "RL10") (pin "7") (pinfunction "7_7") (pintype "bidirectional"))
    )
    (net (code "159") (name "unconnected-(U3-DCDC_LN-Pad12)") (class "Default")
      (node (ref "U3") (pin "12") (pinfunction "DCDC_LN_12") (pintype "bidirectional"))
    )
    (net (code "160") (name "unconnected-(U3-DCDC_LP-Pad11)") (class "Default")
      (node (ref "U3") (pin "11") (pinfunction "DCDC_LP_11") (pintype "bidirectional"))
    )
    (net (code "161") (name "unconnected-(U3-PTC16-Pad45)") (class "Default")
      (node (ref "U3") (pin "45") (pinfunction "PTC16_45") (pintype "bidirectional"))
    )
    (net (code "162") (name "unconnected-(U3-XTAL_OUT-Pad29)") (class "Default")
      (node (ref "U3") (pin "29") (pinfunction "XTAL_OUT_29") (pintype "bidirectional"))
    )
    (net (code "163") (name "unconnected-(U4-NC-Pad3)") (class "Default")
      (node (ref "U4") (pin "3") (pinfunction "NC_3") (pintype "no_connect"))
    )
    (net (code "164") (name "unconnected-(U7-Y4-Pad11)") (class "Default")
      (node (ref "U7") (pin "11") (pinfunction "Y4_11") (pintype "bidirectional"))
    )
    (net (code "165") (name "unconnected-(U7-Y5-Pad10)") (class "Default")
      (node (ref "U7") (pin "10") (pinfunction "Y5_10") (pintype "bidirectional"))
    )
    (net (code "166") (name "unconnected-(U7-Y6-Pad9)") (class "Default")
      (node (ref "U7") (pin "9") (pinfunction "Y6_9") (pintype "bidirectional"))
    )
    (net (code "167") (name "unconnected-(U7-Y7-Pad7)") (class "Default")
      (node (ref "U7") (pin "7") (pinfunction "Y7_7") (pintype "bidirectional"))
    )
    (net (code "168") (name "unconnected-(U10-OUT7-Pad10)") (class "Default")
      (node (ref "U10") (pin "10") (pinfunction "OUT7_10") (pintype "output"))
    )
  )
)
